# NN22_RPi_DetAdapter03_s00.net
KiCad netlist of a schematic drawn in EAGLE
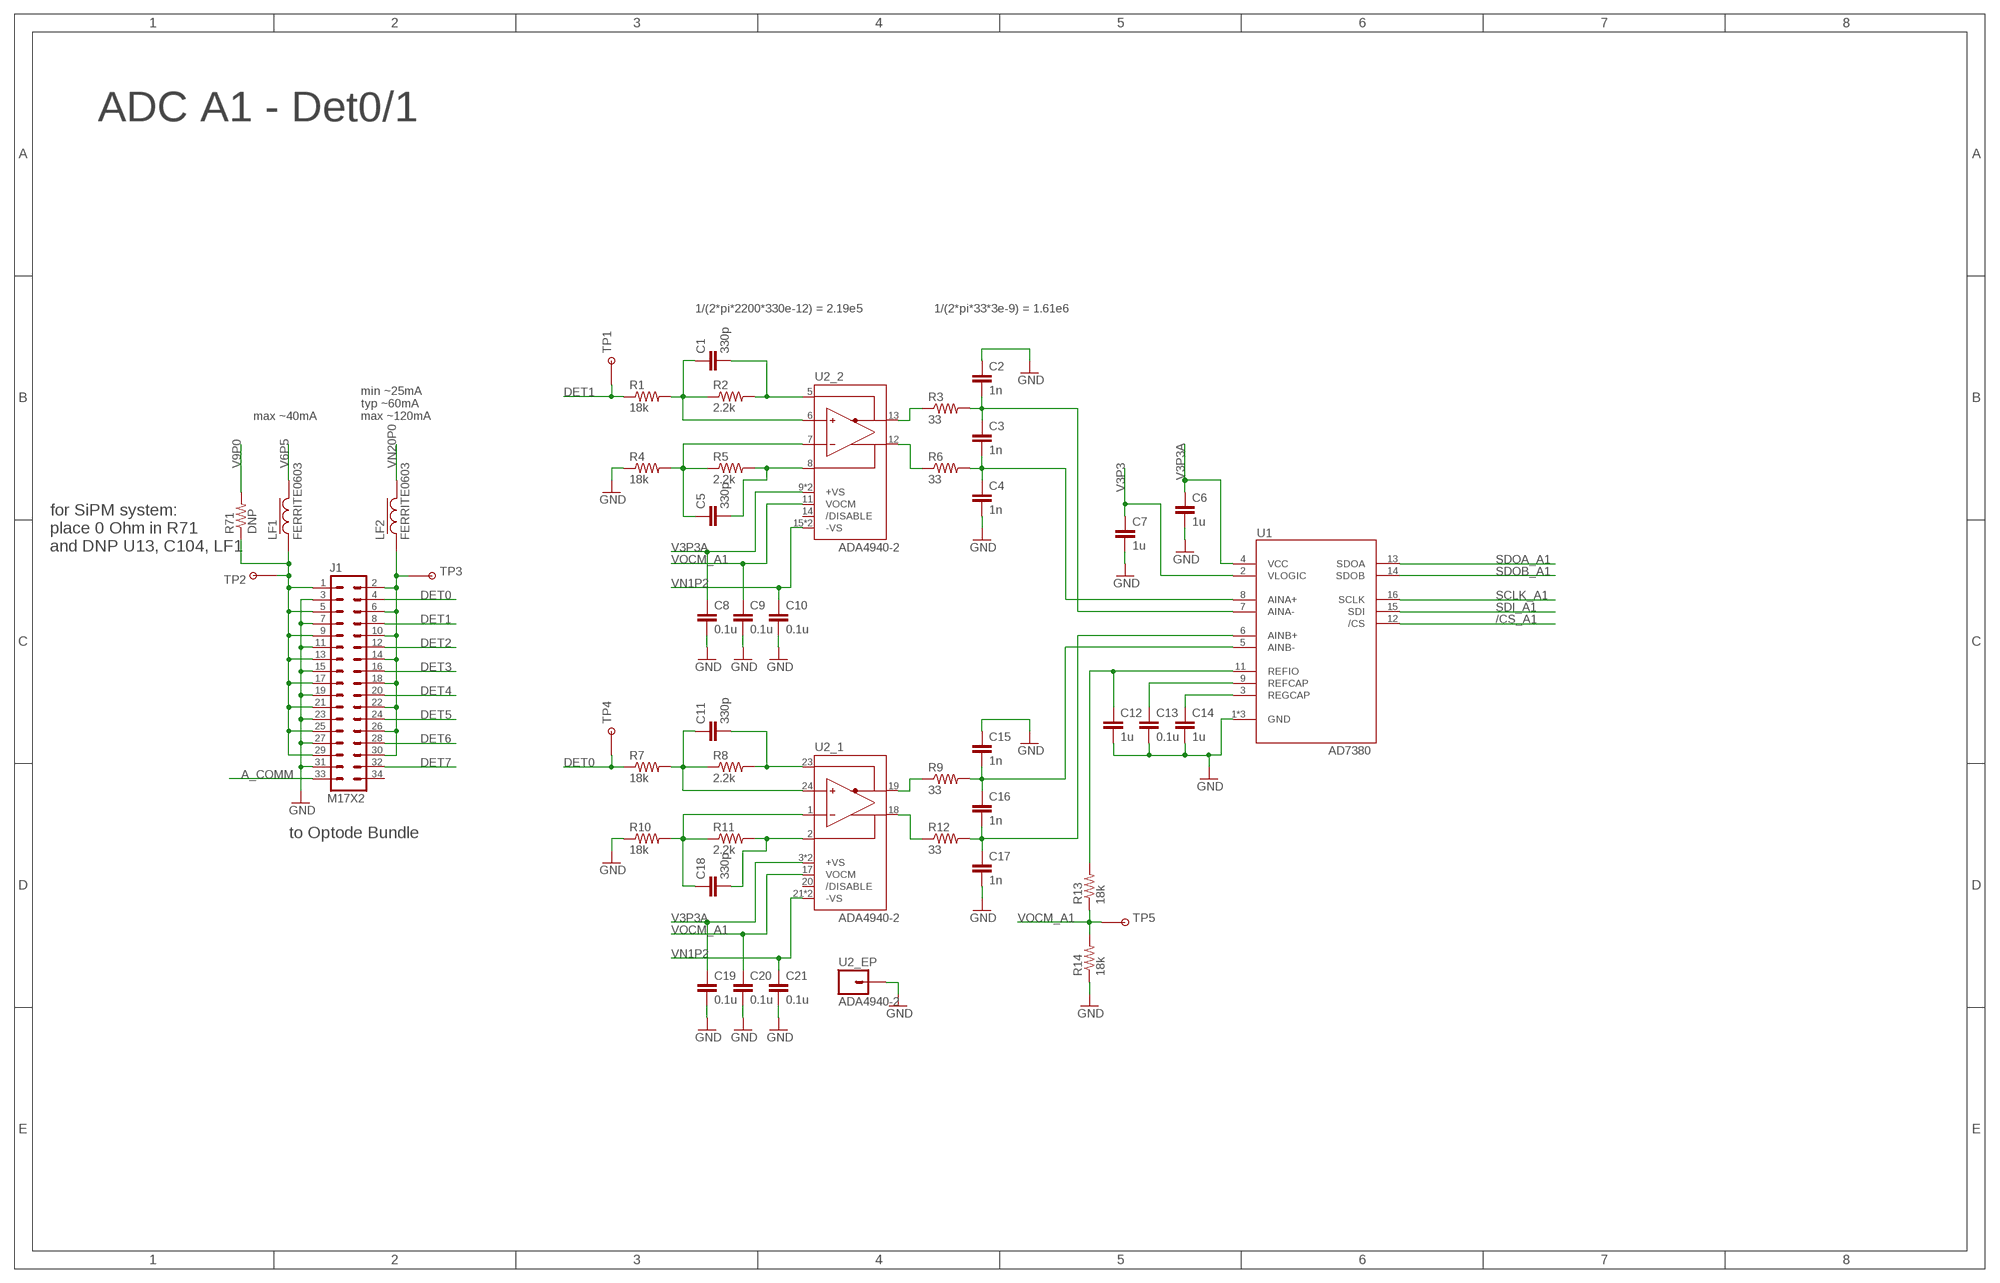
[diagram p0: schematic, sheet 1]
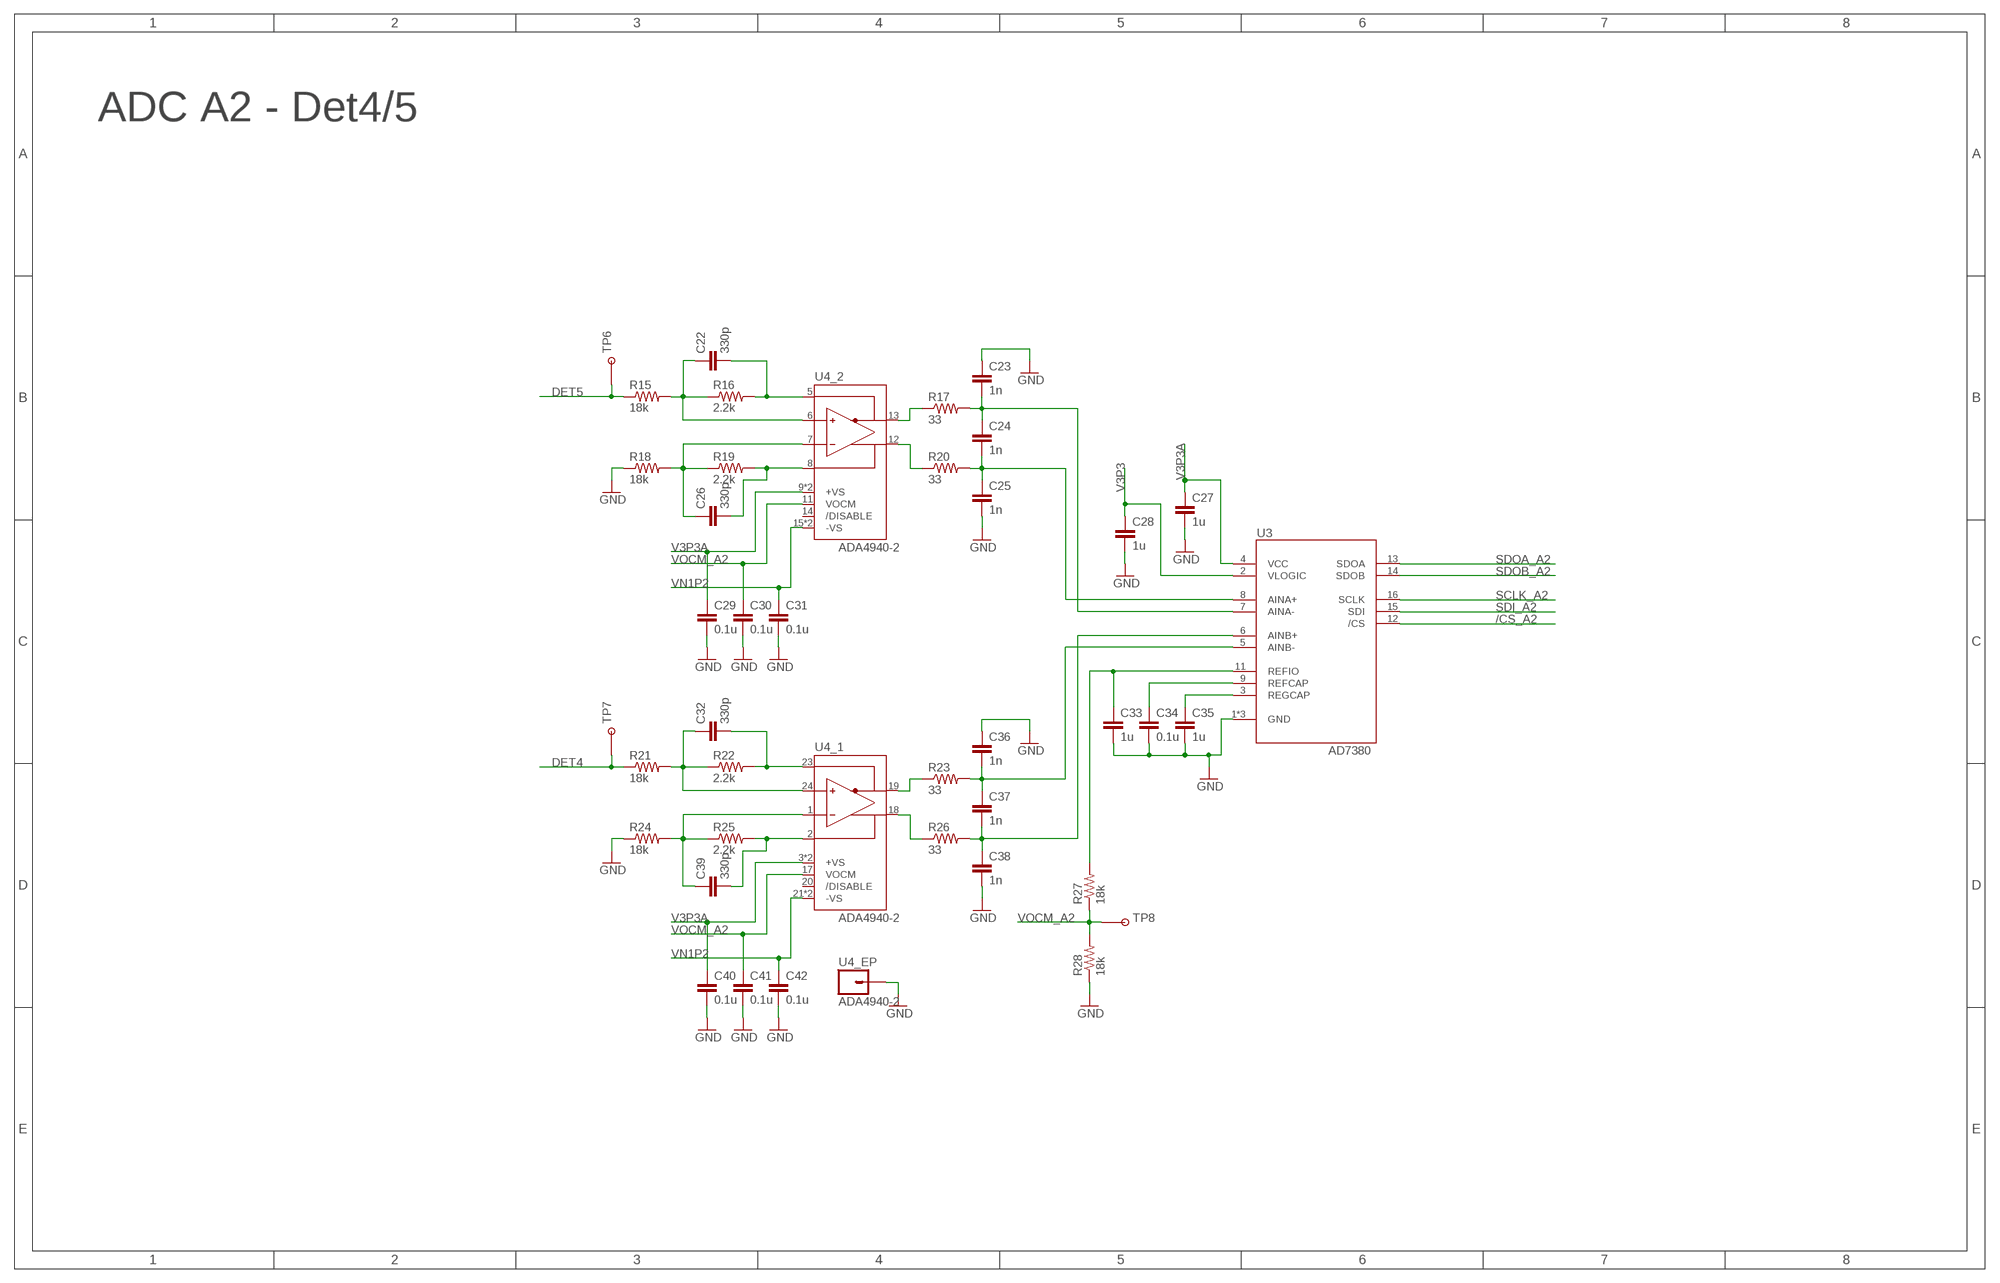
[diagram p1: schematic, sheet 2]
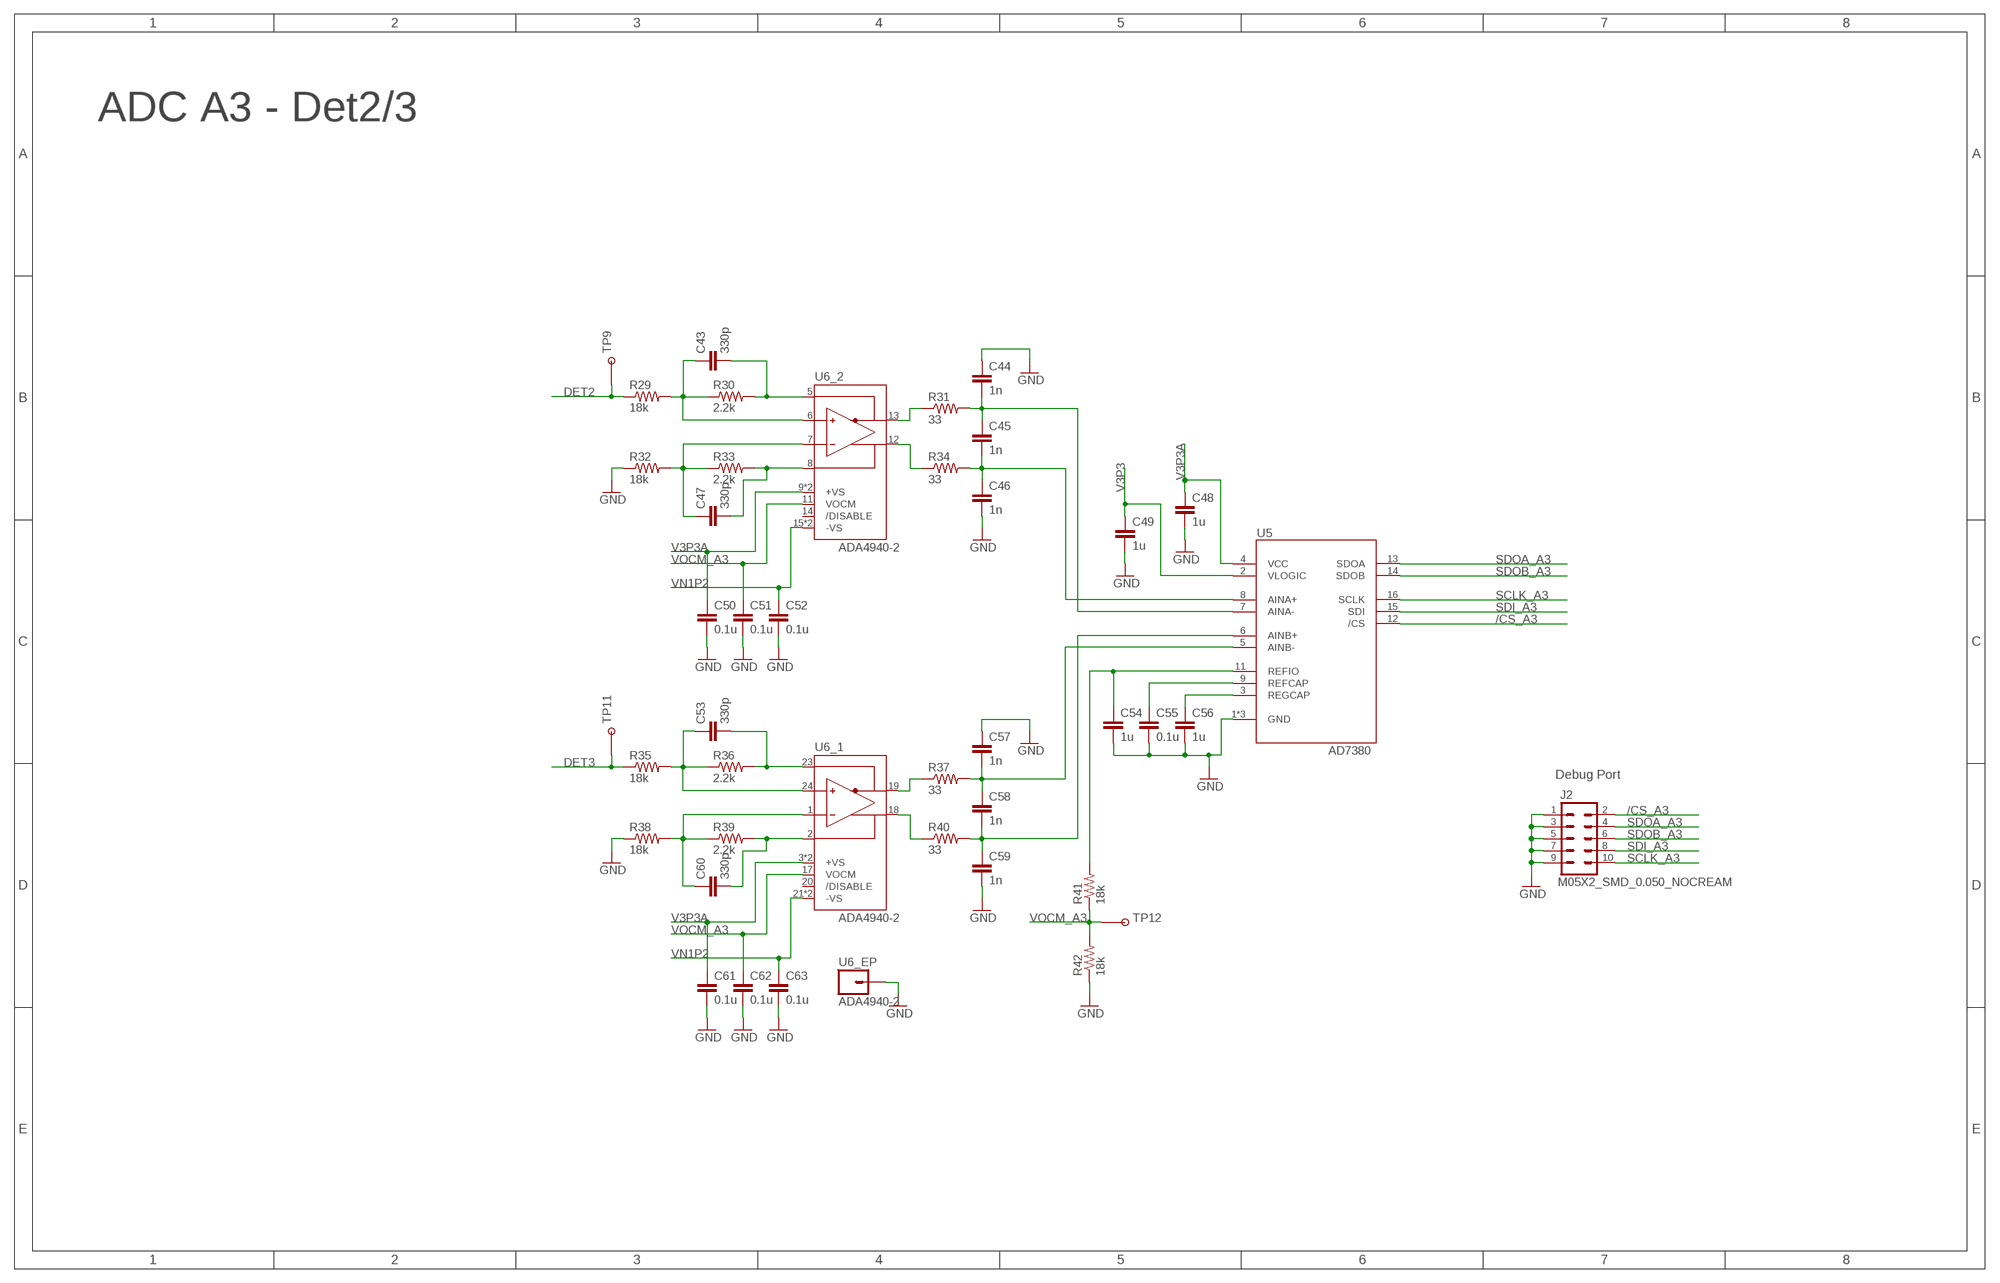
[diagram p2: schematic, sheet 3]
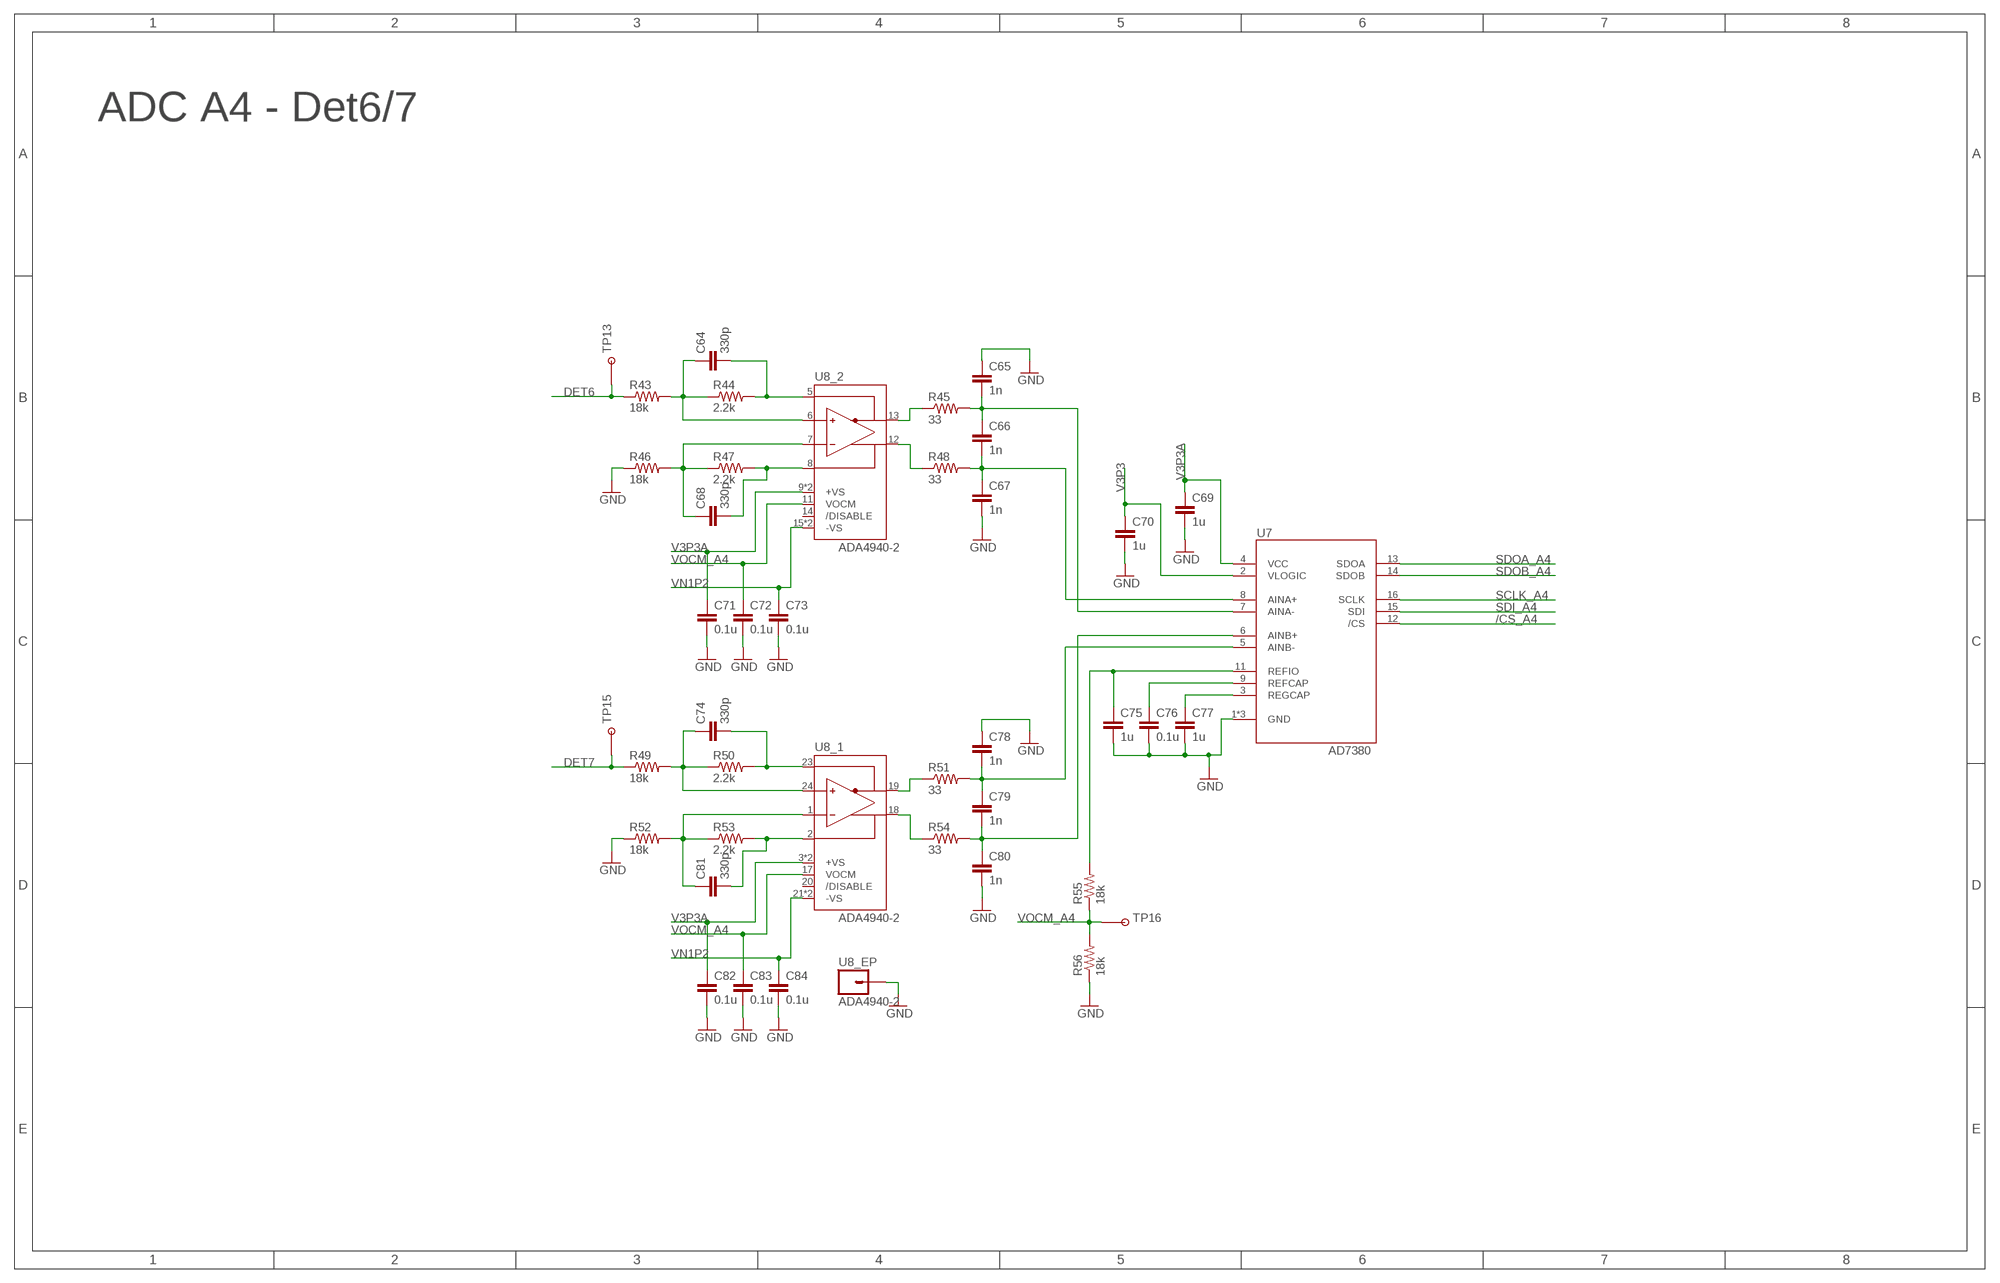
[diagram p3: schematic, sheet 4]
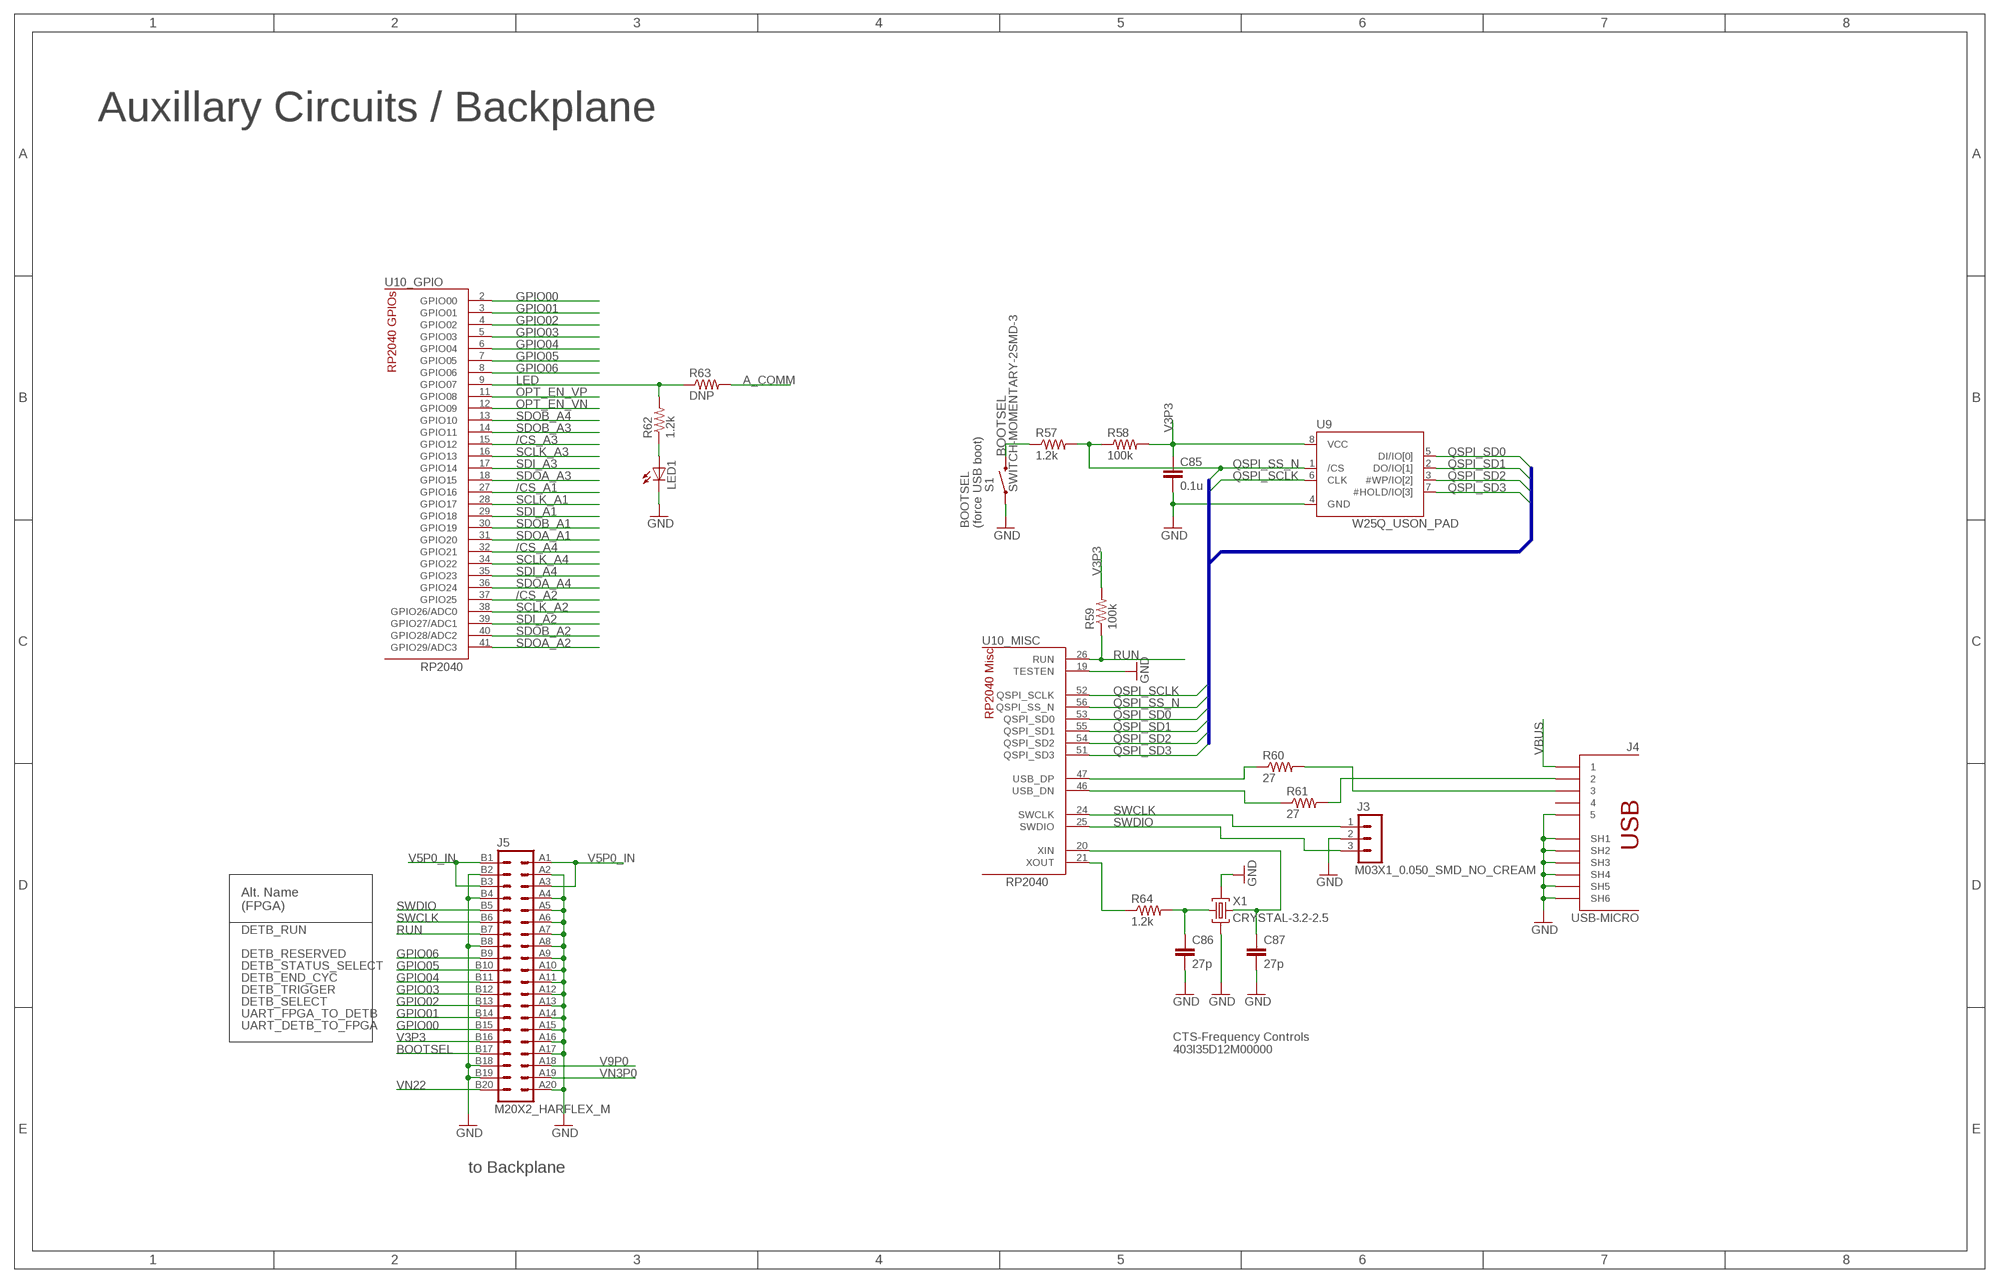
[diagram p4: schematic, sheet 5]
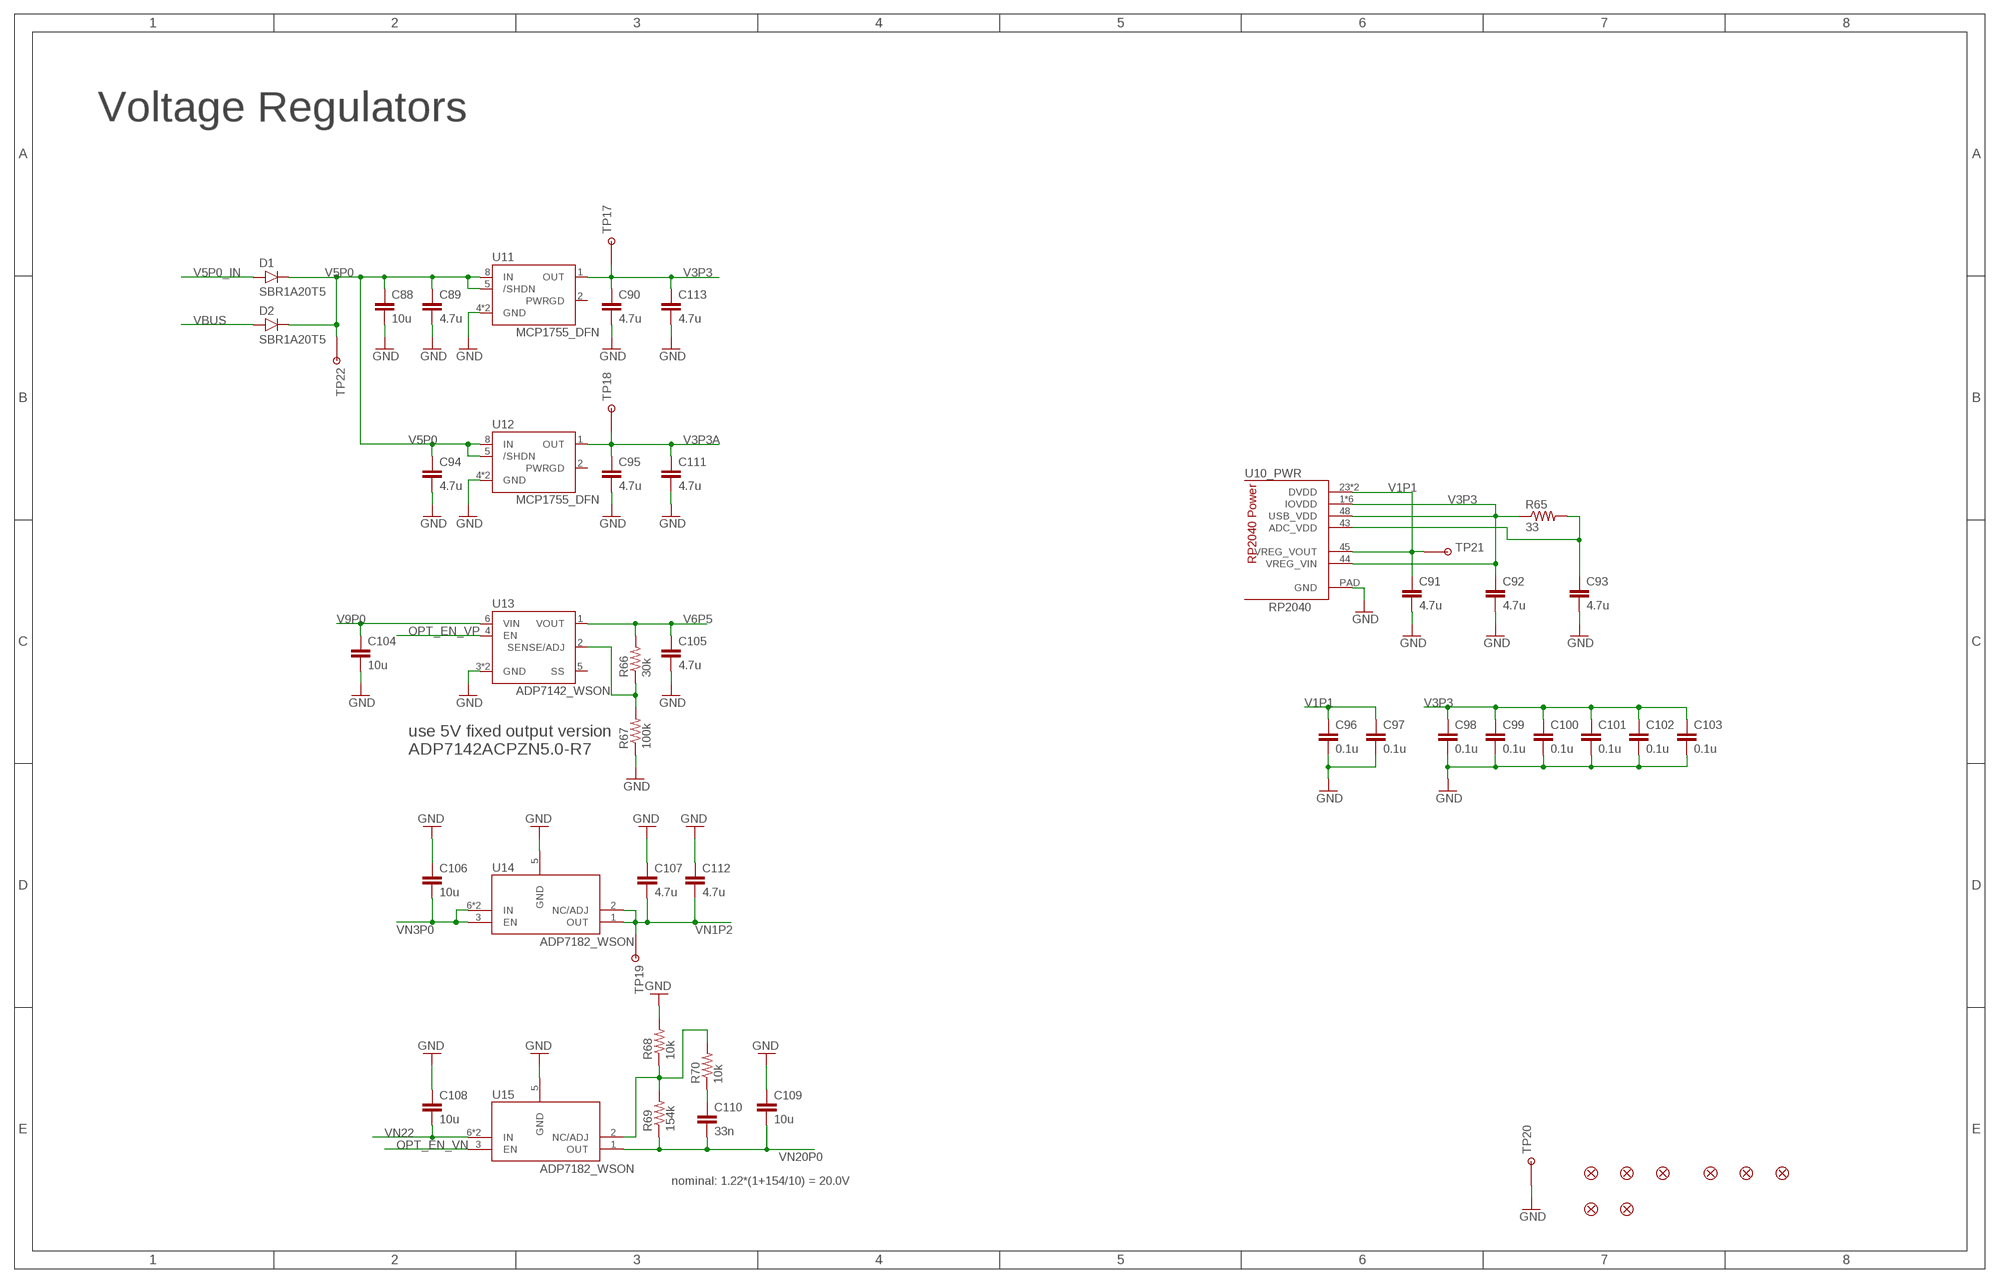
[diagram p5: schematic, sheet 6]

(export (version "E")
  (design (tool "Eeschema 10.0.6"))
  (components
    (comp (ref "C88")
      (value "10u")
      (footprint "eagle-import:0603-CAP")
      (libsource (lib "eagle-import") (part "CAP0603-CAP"))
    )
    (comp (ref "C89")
      (value "4.7u")
      (footprint "eagle-import:0402-CAP")
      (libsource (lib "eagle-import") (part "CAP0402-CAP"))
    )
    (comp (ref "C90")
      (value "4.7u")
      (footprint "eagle-import:0402-CAP")
      (libsource (lib "eagle-import") (part "CAP0402-CAP"))
    )
    (comp (ref "C91")
      (value "4.7u")
      (footprint "eagle-import:0402-CAP")
      (libsource (lib "eagle-import") (part "CAP0402-CAP"))
    )
    (comp (ref "C92")
      (value "4.7u")
      (footprint "eagle-import:0402-CAP")
      (libsource (lib "eagle-import") (part "CAP0402-CAP"))
    )
    (comp (ref "C93")
      (value "4.7u")
      (footprint "eagle-import:0402-CAP")
      (libsource (lib "eagle-import") (part "CAP0402-CAP"))
    )
    (comp (ref "C94")
      (value "4.7u")
      (footprint "eagle-import:0402-CAP")
      (libsource (lib "eagle-import") (part "CAP0402-CAP"))
    )
    (comp (ref "C95")
      (value "4.7u")
      (footprint "eagle-import:0402-CAP")
      (libsource (lib "eagle-import") (part "CAP0402-CAP"))
    )
    (comp (ref "C96")
      (value "0.1u")
      (footprint "eagle-import:0402-CAP")
      (libsource (lib "eagle-import") (part "CAP0402-CAP"))
    )
    (comp (ref "C97")
      (value "0.1u")
      (footprint "eagle-import:0402-CAP")
      (libsource (lib "eagle-import") (part "CAP0402-CAP"))
    )
    (comp (ref "C98")
      (value "0.1u")
      (footprint "eagle-import:0402-CAP")
      (libsource (lib "eagle-import") (part "CAP0402-CAP"))
    )
    (comp (ref "C99")
      (value "0.1u")
      (footprint "eagle-import:0402-CAP")
      (libsource (lib "eagle-import") (part "CAP0402-CAP"))
    )
    (comp (ref "C100")
      (value "0.1u")
      (footprint "eagle-import:0402-CAP")
      (libsource (lib "eagle-import") (part "CAP0402-CAP"))
    )
    (comp (ref "C101")
      (value "0.1u")
      (footprint "eagle-import:0402-CAP")
      (libsource (lib "eagle-import") (part "CAP0402-CAP"))
    )
    (comp (ref "C102")
      (value "0.1u")
      (footprint "eagle-import:0402-CAP")
      (libsource (lib "eagle-import") (part "CAP0402-CAP"))
    )
    (comp (ref "C103")
      (value "0.1u")
      (footprint "eagle-import:0402-CAP")
      (libsource (lib "eagle-import") (part "CAP0402-CAP"))
    )
    (comp (ref "C104")
      (value "10u")
      (footprint "eagle-import:0603-CAP")
      (libsource (lib "eagle-import") (part "CAP0603-CAP"))
    )
    (comp (ref "C105")
      (value "4.7u")
      (footprint "eagle-import:0402-CAP")
      (libsource (lib "eagle-import") (part "CAP0402-CAP"))
    )
    (comp (ref "C106")
      (value "10u")
      (footprint "eagle-import:0603-CAP")
      (libsource (lib "eagle-import") (part "CAP0603-CAP"))
    )
    (comp (ref "C107")
      (value "4.7u")
      (footprint "eagle-import:0402-CAP")
      (libsource (lib "eagle-import") (part "CAP0402-CAP"))
    )
    (comp (ref "C108")
      (value "10u")
      (footprint "eagle-import:0603-CAP")
      (libsource (lib "eagle-import") (part "CAP0603-CAP"))
    )
    (comp (ref "C109")
      (value "10u")
      (footprint "eagle-import:0603-CAP")
      (libsource (lib "eagle-import") (part "CAP0603-CAP"))
    )
    (comp (ref "C110")
      (value "33n")
      (footprint "eagle-import:0402-CAP")
      (libsource (lib "eagle-import") (part "CAP0402-CAP"))
    )
    (comp (ref "C111")
      (value "4.7u")
      (footprint "eagle-import:0402-CAP")
      (libsource (lib "eagle-import") (part "CAP0402-CAP"))
    )
    (comp (ref "C112")
      (value "4.7u")
      (footprint "eagle-import:0402-CAP")
      (libsource (lib "eagle-import") (part "CAP0402-CAP"))
    )
    (comp (ref "C113")
      (value "4.7u")
      (footprint "eagle-import:0402-CAP")
      (libsource (lib "eagle-import") (part "CAP0402-CAP"))
    )
    (comp (ref "D1")
      (value "SBR1A20T5")
      (footprint "eagle-import:SOD523")
      (libsource (lib "eagle-import") (part "DIODE_SOD523"))
    )
    (comp (ref "D2")
      (value "SBR1A20T5")
      (footprint "eagle-import:SOD523")
      (libsource (lib "eagle-import") (part "DIODE_SOD523"))
    )
    (comp (ref "FID1")
      (value "FIDUCIALUFIDUCIAL")
      (footprint "eagle-import:MICRO-FIDUCIAL")
      (libsource (lib "eagle-import") (part "FIDUCIALUFIDUCIAL"))
    )
    (comp (ref "FID2")
      (value "FIDUCIALUFIDUCIAL")
      (footprint "eagle-import:MICRO-FIDUCIAL")
      (libsource (lib "eagle-import") (part "FIDUCIALUFIDUCIAL"))
    )
    (comp (ref "FID3")
      (value "FIDUCIALUFIDUCIAL")
      (footprint "eagle-import:MICRO-FIDUCIAL")
      (libsource (lib "eagle-import") (part "FIDUCIALUFIDUCIAL"))
    )
    (comp (ref "FID4")
      (value "FIDUCIALUFIDUCIAL")
      (footprint "eagle-import:MICRO-FIDUCIAL")
      (libsource (lib "eagle-import") (part "FIDUCIALUFIDUCIAL"))
    )
    (comp (ref "FID5")
      (value "FIDUCIALUFIDUCIAL")
      (footprint "eagle-import:MICRO-FIDUCIAL")
      (libsource (lib "eagle-import") (part "FIDUCIALUFIDUCIAL"))
    )
    (comp (ref "FID6")
      (value "FIDUCIALUFIDUCIAL")
      (footprint "eagle-import:MICRO-FIDUCIAL")
      (libsource (lib "eagle-import") (part "FIDUCIALUFIDUCIAL"))
    )
    (comp (ref "FID7")
      (value "FIDUCIALUFIDUCIAL")
      (footprint "eagle-import:MICRO-FIDUCIAL")
      (libsource (lib "eagle-import") (part "FIDUCIALUFIDUCIAL"))
    )
    (comp (ref "FID8")
      (value "FIDUCIALUFIDUCIAL")
      (footprint "eagle-import:MICRO-FIDUCIAL")
      (libsource (lib "eagle-import") (part "FIDUCIALUFIDUCIAL"))
    )
    (comp (ref "R65")
      (value "33")
      (footprint "eagle-import:0402-RES")
      (libsource (lib "eagle-import") (part "RESISTOR0402-RES"))
    )
    (comp (ref "R66")
      (value "30k")
      (footprint "eagle-import:0402-RES")
      (libsource (lib "eagle-import") (part "RESISTOR0402-RES"))
    )
    (comp (ref "R67")
      (value "100k")
      (footprint "eagle-import:0402-RES")
      (libsource (lib "eagle-import") (part "RESISTOR0402-RES"))
    )
    (comp (ref "R68")
      (value "10k")
      (footprint "eagle-import:0402-RES")
      (libsource (lib "eagle-import") (part "RESISTOR0402-RES"))
    )
    (comp (ref "R69")
      (value "154k")
      (footprint "eagle-import:0402-RES")
      (libsource (lib "eagle-import") (part "RESISTOR0402-RES"))
    )
    (comp (ref "R70")
      (value "10k")
      (footprint "eagle-import:0402-RES")
      (libsource (lib "eagle-import") (part "RESISTOR0402-RES"))
    )
    (comp (ref "TP17")
      (value "TESTPOINT_ROUND")
      (footprint "eagle-import:TESTPAD_ROUND")
      (libsource (lib "eagle-import") (part "TESTPOINT_ROUND"))
    )
    (comp (ref "TP18")
      (value "TESTPOINT_ROUND")
      (footprint "eagle-import:TESTPAD_ROUND")
      (libsource (lib "eagle-import") (part "TESTPOINT_ROUND"))
    )
    (comp (ref "TP19")
      (value "TESTPOINT_ROUND")
      (footprint "eagle-import:TESTPAD_ROUND")
      (libsource (lib "eagle-import") (part "TESTPOINT_ROUND"))
    )
    (comp (ref "TP20")
      (value "TESTPOINT1X01")
      (footprint "eagle-import:1X01")
      (libsource (lib "eagle-import") (part "TESTPOINT1X01"))
    )
    (comp (ref "TP21")
      (value "TESTPOINTPADSMALL")
      (footprint "eagle-import:TESTPAD_SMALL")
      (libsource (lib "eagle-import") (part "TESTPOINTPADSMALL"))
    )
    (comp (ref "TP22")
      (value "TESTPOINT_ROUND")
      (footprint "eagle-import:TESTPAD_ROUND")
      (libsource (lib "eagle-import") (part "TESTPOINT_ROUND"))
    )
    (comp (ref "U10")
      (value "RP2040")
      (footprint "eagle-import:QFN-56_EP")
      (libsource (lib "eagle-import") (part "RP2040"))
    )
    (comp (ref "U11")
      (value "MCP1755_DFN")
      (footprint "eagle-import:DFN8_2X3MM")
      (libsource (lib "eagle-import") (part "MCP1755_DFN"))
    )
    (comp (ref "U12")
      (value "MCP1755_DFN")
      (footprint "eagle-import:DFN8_2X3MM")
      (libsource (lib "eagle-import") (part "MCP1755_DFN"))
    )
    (comp (ref "U13")
      (value "ADP7142_WSON")
      (footprint "eagle-import:WSON6")
      (libsource (lib "eagle-import") (part "ADP7142_WSON"))
    )
    (comp (ref "U14")
      (value "ADP7182_WSON")
      (footprint "eagle-import:WSON6")
      (libsource (lib "eagle-import") (part "ADP7182_WSON"))
    )
    (comp (ref "U15")
      (value "ADP7182_WSON")
      (footprint "eagle-import:WSON6")
      (libsource (lib "eagle-import") (part "ADP7182_WSON"))
    )
    (comp (ref "C1")
      (value "330p")
      (footprint "eagle-import:0402-CAP")
      (libsource (lib "eagle-import") (part "CAP0402-CAP"))
    )
    (comp (ref "C2")
      (value "1n")
      (footprint "eagle-import:0402-CAP")
      (libsource (lib "eagle-import") (part "CAP0402-CAP"))
    )
    (comp (ref "C3")
      (value "1n")
      (footprint "eagle-import:0402-CAP")
      (libsource (lib "eagle-import") (part "CAP0402-CAP"))
    )
    (comp (ref "C4")
      (value "1n")
      (footprint "eagle-import:0402-CAP")
      (libsource (lib "eagle-import") (part "CAP0402-CAP"))
    )
    (comp (ref "C5")
      (value "330p")
      (footprint "eagle-import:0402-CAP")
      (libsource (lib "eagle-import") (part "CAP0402-CAP"))
    )
    (comp (ref "C6")
      (value "1u")
      (footprint "eagle-import:0402-CAP")
      (libsource (lib "eagle-import") (part "CAP0402-CAP"))
    )
    (comp (ref "C7")
      (value "1u")
      (footprint "eagle-import:0402-CAP")
      (libsource (lib "eagle-import") (part "CAP0402-CAP"))
    )
    (comp (ref "C8")
      (value "0.1u")
      (footprint "eagle-import:0402-CAP")
      (libsource (lib "eagle-import") (part "CAP0402-CAP"))
    )
    (comp (ref "C9")
      (value "0.1u")
      (footprint "eagle-import:0402-CAP")
      (libsource (lib "eagle-import") (part "CAP0402-CAP"))
    )
    (comp (ref "C10")
      (value "0.1u")
      (footprint "eagle-import:0402-CAP")
      (libsource (lib "eagle-import") (part "CAP0402-CAP"))
    )
    (comp (ref "C11")
      (value "330p")
      (footprint "eagle-import:0402-CAP")
      (libsource (lib "eagle-import") (part "CAP0402-CAP"))
    )
    (comp (ref "C12")
      (value "1u")
      (footprint "eagle-import:0402-CAP")
      (libsource (lib "eagle-import") (part "CAP0402-CAP"))
    )
    (comp (ref "C13")
      (value "0.1u")
      (footprint "eagle-import:0402-CAP")
      (libsource (lib "eagle-import") (part "CAP0402-CAP"))
    )
    (comp (ref "C14")
      (value "1u")
      (footprint "eagle-import:0402-CAP")
      (libsource (lib "eagle-import") (part "CAP0402-CAP"))
    )
    (comp (ref "C15")
      (value "1n")
      (footprint "eagle-import:0402-CAP")
      (libsource (lib "eagle-import") (part "CAP0402-CAP"))
    )
    (comp (ref "C16")
      (value "1n")
      (footprint "eagle-import:0402-CAP")
      (libsource (lib "eagle-import") (part "CAP0402-CAP"))
    )
    (comp (ref "C17")
      (value "1n")
      (footprint "eagle-import:0402-CAP")
      (libsource (lib "eagle-import") (part "CAP0402-CAP"))
    )
    (comp (ref "C18")
      (value "330p")
      (footprint "eagle-import:0402-CAP")
      (libsource (lib "eagle-import") (part "CAP0402-CAP"))
    )
    (comp (ref "C19")
      (value "0.1u")
      (footprint "eagle-import:0402-CAP")
      (libsource (lib "eagle-import") (part "CAP0402-CAP"))
    )
    (comp (ref "C20")
      (value "0.1u")
      (footprint "eagle-import:0402-CAP")
      (libsource (lib "eagle-import") (part "CAP0402-CAP"))
    )
    (comp (ref "C21")
      (value "0.1u")
      (footprint "eagle-import:0402-CAP")
      (libsource (lib "eagle-import") (part "CAP0402-CAP"))
    )
    (comp (ref "J1")
      (value "M17X2")
      (footprint "eagle-import:M17X2_0.050_SHF")
      (libsource (lib "eagle-import") (part "M17X2"))
    )
    (comp (ref "LF1")
      (value "FERRITE0603")
      (footprint "eagle-import:0603-FER")
      (libsource (lib "eagle-import") (part "FERRITE0603"))
    )
    (comp (ref "LF2")
      (value "FERRITE0603")
      (footprint "eagle-import:0603-FER")
      (libsource (lib "eagle-import") (part "FERRITE0603"))
    )
    (comp (ref "R1")
      (value "18k")
      (footprint "eagle-import:0402-RES")
      (libsource (lib "eagle-import") (part "RESISTOR0402-RES"))
    )
    (comp (ref "R2")
      (value "2.2k")
      (footprint "eagle-import:0402-RES")
      (libsource (lib "eagle-import") (part "RESISTOR0402-RES"))
    )
    (comp (ref "R3")
      (value "33")
      (footprint "eagle-import:0402-RES")
      (libsource (lib "eagle-import") (part "RESISTOR0402-RES"))
    )
    (comp (ref "R4")
      (value "18k")
      (footprint "eagle-import:0402-RES")
      (libsource (lib "eagle-import") (part "RESISTOR0402-RES"))
    )
    (comp (ref "R5")
      (value "2.2k")
      (footprint "eagle-import:0402-RES")
      (libsource (lib "eagle-import") (part "RESISTOR0402-RES"))
    )
    (comp (ref "R6")
      (value "33")
      (footprint "eagle-import:0402-RES")
      (libsource (lib "eagle-import") (part "RESISTOR0402-RES"))
    )
    (comp (ref "R7")
      (value "18k")
      (footprint "eagle-import:0402-RES")
      (libsource (lib "eagle-import") (part "RESISTOR0402-RES"))
    )
    (comp (ref "R8")
      (value "2.2k")
      (footprint "eagle-import:0402-RES")
      (libsource (lib "eagle-import") (part "RESISTOR0402-RES"))
    )
    (comp (ref "R9")
      (value "33")
      (footprint "eagle-import:0402-RES")
      (libsource (lib "eagle-import") (part "RESISTOR0402-RES"))
    )
    (comp (ref "R10")
      (value "18k")
      (footprint "eagle-import:0402-RES")
      (libsource (lib "eagle-import") (part "RESISTOR0402-RES"))
    )
    (comp (ref "R11")
      (value "2.2k")
      (footprint "eagle-import:0402-RES")
      (libsource (lib "eagle-import") (part "RESISTOR0402-RES"))
    )
    (comp (ref "R12")
      (value "33")
      (footprint "eagle-import:0402-RES")
      (libsource (lib "eagle-import") (part "RESISTOR0402-RES"))
    )
    (comp (ref "R13")
      (value "18k")
      (footprint "eagle-import:0402-RES")
      (libsource (lib "eagle-import") (part "RESISTOR0402-RES"))
    )
    (comp (ref "R14")
      (value "18k")
      (footprint "eagle-import:0402-RES")
      (libsource (lib "eagle-import") (part "RESISTOR0402-RES"))
    )
    (comp (ref "R71")
      (value "DNP")
      (footprint "eagle-import:0402-RES")
      (libsource (lib "eagle-import") (part "RESISTOR0402-RES"))
    )
    (comp (ref "TP1")
      (value "TESTPOINT_ROUND")
      (footprint "eagle-import:TESTPAD_ROUND")
      (libsource (lib "eagle-import") (part "TESTPOINT_ROUND"))
    )
    (comp (ref "TP2")
      (value "TESTPOINT_ROUND")
      (footprint "eagle-import:TESTPAD_ROUND")
      (libsource (lib "eagle-import") (part "TESTPOINT_ROUND"))
    )
    (comp (ref "TP3")
      (value "TESTPOINT_ROUND")
      (footprint "eagle-import:TESTPAD_ROUND")
      (libsource (lib "eagle-import") (part "TESTPOINT_ROUND"))
    )
    (comp (ref "TP4")
      (value "TESTPOINT_ROUND")
      (footprint "eagle-import:TESTPAD_ROUND")
      (libsource (lib "eagle-import") (part "TESTPOINT_ROUND"))
    )
    (comp (ref "TP5")
      (value "TESTPOINT_ROUND")
      (footprint "eagle-import:TESTPAD_ROUND")
      (libsource (lib "eagle-import") (part "TESTPOINT_ROUND"))
    )
    (comp (ref "U1")
      (value "AD7380")
      (footprint "eagle-import:LFCSP16")
      (libsource (lib "eagle-import") (part "AD7380"))
    )
    (comp (ref "U2")
      (value "ADA4940-2")
      (footprint "eagle-import:LFCSP24")
      (libsource (lib "eagle-import") (part "ADA4940-2"))
    )
    (comp (ref "C64")
      (value "330p")
      (footprint "eagle-import:0402-CAP")
      (libsource (lib "eagle-import") (part "CAP0402-CAP"))
    )
    (comp (ref "C65")
      (value "1n")
      (footprint "eagle-import:0402-CAP")
      (libsource (lib "eagle-import") (part "CAP0402-CAP"))
    )
    (comp (ref "C66")
      (value "1n")
      (footprint "eagle-import:0402-CAP")
      (libsource (lib "eagle-import") (part "CAP0402-CAP"))
    )
    (comp (ref "C67")
      (value "1n")
      (footprint "eagle-import:0402-CAP")
      (libsource (lib "eagle-import") (part "CAP0402-CAP"))
    )
    (comp (ref "C68")
      (value "330p")
      (footprint "eagle-import:0402-CAP")
      (libsource (lib "eagle-import") (part "CAP0402-CAP"))
    )
    (comp (ref "C69")
      (value "1u")
      (footprint "eagle-import:0402-CAP")
      (libsource (lib "eagle-import") (part "CAP0402-CAP"))
    )
    (comp (ref "C70")
      (value "1u")
      (footprint "eagle-import:0402-CAP")
      (libsource (lib "eagle-import") (part "CAP0402-CAP"))
    )
    (comp (ref "C71")
      (value "0.1u")
      (footprint "eagle-import:0402-CAP")
      (libsource (lib "eagle-import") (part "CAP0402-CAP"))
    )
    (comp (ref "C72")
      (value "0.1u")
      (footprint "eagle-import:0402-CAP")
      (libsource (lib "eagle-import") (part "CAP0402-CAP"))
    )
    (comp (ref "C73")
      (value "0.1u")
      (footprint "eagle-import:0402-CAP")
      (libsource (lib "eagle-import") (part "CAP0402-CAP"))
    )
    (comp (ref "C74")
      (value "330p")
      (footprint "eagle-import:0402-CAP")
      (libsource (lib "eagle-import") (part "CAP0402-CAP"))
    )
    (comp (ref "C75")
      (value "1u")
      (footprint "eagle-import:0402-CAP")
      (libsource (lib "eagle-import") (part "CAP0402-CAP"))
    )
    (comp (ref "C76")
      (value "0.1u")
      (footprint "eagle-import:0402-CAP")
      (libsource (lib "eagle-import") (part "CAP0402-CAP"))
    )
    (comp (ref "C77")
      (value "1u")
      (footprint "eagle-import:0402-CAP")
      (libsource (lib "eagle-import") (part "CAP0402-CAP"))
    )
    (comp (ref "C78")
      (value "1n")
      (footprint "eagle-import:0402-CAP")
      (libsource (lib "eagle-import") (part "CAP0402-CAP"))
    )
    (comp (ref "C79")
      (value "1n")
      (footprint "eagle-import:0402-CAP")
      (libsource (lib "eagle-import") (part "CAP0402-CAP"))
    )
    (comp (ref "C80")
      (value "1n")
      (footprint "eagle-import:0402-CAP")
      (libsource (lib "eagle-import") (part "CAP0402-CAP"))
    )
    (comp (ref "C81")
      (value "330p")
      (footprint "eagle-import:0402-CAP")
      (libsource (lib "eagle-import") (part "CAP0402-CAP"))
    )
    (comp (ref "C82")
      (value "0.1u")
      (footprint "eagle-import:0402-CAP")
      (libsource (lib "eagle-import") (part "CAP0402-CAP"))
    )
    (comp (ref "C83")
      (value "0.1u")
      (footprint "eagle-import:0402-CAP")
      (libsource (lib "eagle-import") (part "CAP0402-CAP"))
    )
    (comp (ref "C84")
      (value "0.1u")
      (footprint "eagle-import:0402-CAP")
      (libsource (lib "eagle-import") (part "CAP0402-CAP"))
    )
    (comp (ref "R43")
      (value "18k")
      (footprint "eagle-import:0402-RES")
      (libsource (lib "eagle-import") (part "RESISTOR0402-RES"))
    )
    (comp (ref "R44")
      (value "2.2k")
      (footprint "eagle-import:0402-RES")
      (libsource (lib "eagle-import") (part "RESISTOR0402-RES"))
    )
    (comp (ref "R45")
      (value "33")
      (footprint "eagle-import:0402-RES")
      (libsource (lib "eagle-import") (part "RESISTOR0402-RES"))
    )
    (comp (ref "R46")
      (value "18k")
      (footprint "eagle-import:0402-RES")
      (libsource (lib "eagle-import") (part "RESISTOR0402-RES"))
    )
    (comp (ref "R47")
      (value "2.2k")
      (footprint "eagle-import:0402-RES")
      (libsource (lib "eagle-import") (part "RESISTOR0402-RES"))
    )
    (comp (ref "R48")
      (value "33")
      (footprint "eagle-import:0402-RES")
      (libsource (lib "eagle-import") (part "RESISTOR0402-RES"))
    )
    (comp (ref "R49")
      (value "18k")
      (footprint "eagle-import:0402-RES")
      (libsource (lib "eagle-import") (part "RESISTOR0402-RES"))
    )
    (comp (ref "R50")
      (value "2.2k")
      (footprint "eagle-import:0402-RES")
      (libsource (lib "eagle-import") (part "RESISTOR0402-RES"))
    )
    (comp (ref "R51")
      (value "33")
      (footprint "eagle-import:0402-RES")
      (libsource (lib "eagle-import") (part "RESISTOR0402-RES"))
    )
    (comp (ref "R52")
      (value "18k")
      (footprint "eagle-import:0402-RES")
      (libsource (lib "eagle-import") (part "RESISTOR0402-RES"))
    )
    (comp (ref "R53")
      (value "2.2k")
      (footprint "eagle-import:0402-RES")
      (libsource (lib "eagle-import") (part "RESISTOR0402-RES"))
    )
    (comp (ref "R54")
      (value "33")
      (footprint "eagle-import:0402-RES")
      (libsource (lib "eagle-import") (part "RESISTOR0402-RES"))
    )
    (comp (ref "R55")
      (value "18k")
      (footprint "eagle-import:0402-RES")
      (libsource (lib "eagle-import") (part "RESISTOR0402-RES"))
    )
    (comp (ref "R56")
      (value "18k")
      (footprint "eagle-import:0402-RES")
      (libsource (lib "eagle-import") (part "RESISTOR0402-RES"))
    )
    (comp (ref "TP13")
      (value "TESTPOINT_ROUND")
      (footprint "eagle-import:TESTPAD_ROUND")
      (libsource (lib "eagle-import") (part "TESTPOINT_ROUND"))
    )
    (comp (ref "TP15")
      (value "TESTPOINT_ROUND")
      (footprint "eagle-import:TESTPAD_ROUND")
      (libsource (lib "eagle-import") (part "TESTPOINT_ROUND"))
    )
    (comp (ref "TP16")
      (value "TESTPOINT_ROUND")
      (footprint "eagle-import:TESTPAD_ROUND")
      (libsource (lib "eagle-import") (part "TESTPOINT_ROUND"))
    )
    (comp (ref "U7")
      (value "AD7380")
      (footprint "eagle-import:LFCSP16")
      (libsource (lib "eagle-import") (part "AD7380"))
    )
    (comp (ref "U8")
      (value "ADA4940-2")
      (footprint "eagle-import:LFCSP24")
      (libsource (lib "eagle-import") (part "ADA4940-2"))
    )
    (comp (ref "C85")
      (value "0.1u")
      (footprint "eagle-import:0402-CAP")
      (libsource (lib "eagle-import") (part "CAP0402-CAP"))
    )
    (comp (ref "C86")
      (value "27p")
      (footprint "eagle-import:0402-CAP")
      (libsource (lib "eagle-import") (part "CAP0402-CAP"))
    )
    (comp (ref "C87")
      (value "27p")
      (footprint "eagle-import:0402-CAP")
      (libsource (lib "eagle-import") (part "CAP0402-CAP"))
    )
    (comp (ref "J3")
      (value "M03X1_0.050_SMD_NO_CREAM")
      (footprint "eagle-import:M03X1_0.050_SMD_NO_CREAM")
      (libsource (lib "eagle-import") (part "M03X1_0.050_SMD_NO_CREAM"))
    )
    (comp (ref "J4")
      (value "USB-MICRO")
      (footprint "eagle-import:USB-MICRO")
      (libsource (lib "eagle-import") (part "USB-MICRO"))
    )
    (comp (ref "J5")
      (value "M20X2_HARFLEX_M")
      (footprint "eagle-import:M20X2_HARFLEX_M")
      (libsource (lib "eagle-import") (part "M20X2_HARFLEX_M"))
    )
    (comp (ref "LED1")
      (value "LED0603")
      (footprint "eagle-import:LED-0603")
      (libsource (lib "eagle-import") (part "LED0603"))
    )
    (comp (ref "R57")
      (value "1.2k")
      (footprint "eagle-import:0402-RES")
      (libsource (lib "eagle-import") (part "RESISTOR0402-RES"))
    )
    (comp (ref "R58")
      (value "100k")
      (footprint "eagle-import:0402-RES")
      (libsource (lib "eagle-import") (part "RESISTOR0402-RES"))
    )
    (comp (ref "R59")
      (value "100k")
      (footprint "eagle-import:0402-RES")
      (libsource (lib "eagle-import") (part "RESISTOR0402-RES"))
    )
    (comp (ref "R60")
      (value "27")
      (footprint "eagle-import:0402-RES")
      (libsource (lib "eagle-import") (part "RESISTOR0402-RES"))
    )
    (comp (ref "R61")
      (value "27")
      (footprint "eagle-import:0402-RES")
      (libsource (lib "eagle-import") (part "RESISTOR0402-RES"))
    )
    (comp (ref "R62")
      (value "1.2k")
      (footprint "eagle-import:0402-RES")
      (libsource (lib "eagle-import") (part "RESISTOR0402-RES"))
    )
    (comp (ref "R63")
      (value "DNP")
      (footprint "eagle-import:0402-RES")
      (libsource (lib "eagle-import") (part "RESISTOR0402-RES"))
    )
    (comp (ref "R64")
      (value "1.2k")
      (footprint "eagle-import:0402-RES")
      (libsource (lib "eagle-import") (part "RESISTOR0402-RES"))
    )
    (comp (ref "S1")
      (value "SWITCH-MOMENTARY-2SMD-3")
      (footprint "eagle-import:TACTILE_SWITCH_SMD-3")
      (libsource (lib "eagle-import") (part "SWITCH-MOMENTARY-2SMD-3"))
    )
    (comp (ref "U9")
      (value "W25Q_USON_PAD")
      (footprint "eagle-import:USON8L-2X3MM_APM")
      (libsource (lib "eagle-import") (part "W25Q_USON_PAD"))
    )
    (comp (ref "X1")
      (value "CRYSTAL-3.2-2.5")
      (footprint "eagle-import:CRYSTAL-3.2-2.5")
      (libsource (lib "eagle-import") (part "CRYSTAL-3.2-2.5"))
    )
    (comp (ref "C43")
      (value "330p")
      (footprint "eagle-import:0402-CAP")
      (libsource (lib "eagle-import") (part "CAP0402-CAP"))
    )
    (comp (ref "C44")
      (value "1n")
      (footprint "eagle-import:0402-CAP")
      (libsource (lib "eagle-import") (part "CAP0402-CAP"))
    )
    (comp (ref "C45")
      (value "1n")
      (footprint "eagle-import:0402-CAP")
      (libsource (lib "eagle-import") (part "CAP0402-CAP"))
    )
    (comp (ref "C46")
      (value "1n")
      (footprint "eagle-import:0402-CAP")
      (libsource (lib "eagle-import") (part "CAP0402-CAP"))
    )
    (comp (ref "C47")
      (value "330p")
      (footprint "eagle-import:0402-CAP")
      (libsource (lib "eagle-import") (part "CAP0402-CAP"))
    )
    (comp (ref "C48")
      (value "1u")
      (footprint "eagle-import:0402-CAP")
      (libsource (lib "eagle-import") (part "CAP0402-CAP"))
    )
    (comp (ref "C49")
      (value "1u")
      (footprint "eagle-import:0402-CAP")
      (libsource (lib "eagle-import") (part "CAP0402-CAP"))
    )
    (comp (ref "C50")
      (value "0.1u")
      (footprint "eagle-import:0402-CAP")
      (libsource (lib "eagle-import") (part "CAP0402-CAP"))
    )
    (comp (ref "C51")
      (value "0.1u")
      (footprint "eagle-import:0402-CAP")
      (libsource (lib "eagle-import") (part "CAP0402-CAP"))
    )
    (comp (ref "C52")
      (value "0.1u")
      (footprint "eagle-import:0402-CAP")
      (libsource (lib "eagle-import") (part "CAP0402-CAP"))
    )
    (comp (ref "C53")
      (value "330p")
      (footprint "eagle-import:0402-CAP")
      (libsource (lib "eagle-import") (part "CAP0402-CAP"))
    )
    (comp (ref "C54")
      (value "1u")
      (footprint "eagle-import:0402-CAP")
      (libsource (lib "eagle-import") (part "CAP0402-CAP"))
    )
    (comp (ref "C55")
      (value "0.1u")
      (footprint "eagle-import:0402-CAP")
      (libsource (lib "eagle-import") (part "CAP0402-CAP"))
    )
    (comp (ref "C56")
      (value "1u")
      (footprint "eagle-import:0402-CAP")
      (libsource (lib "eagle-import") (part "CAP0402-CAP"))
    )
    (comp (ref "C57")
      (value "1n")
      (footprint "eagle-import:0402-CAP")
      (libsource (lib "eagle-import") (part "CAP0402-CAP"))
    )
    (comp (ref "C58")
      (value "1n")
      (footprint "eagle-import:0402-CAP")
      (libsource (lib "eagle-import") (part "CAP0402-CAP"))
    )
    (comp (ref "C59")
      (value "1n")
      (footprint "eagle-import:0402-CAP")
      (libsource (lib "eagle-import") (part "CAP0402-CAP"))
    )
    (comp (ref "C60")
      (value "330p")
      (footprint "eagle-import:0402-CAP")
      (libsource (lib "eagle-import") (part "CAP0402-CAP"))
    )
    (comp (ref "C61")
      (value "0.1u")
      (footprint "eagle-import:0402-CAP")
      (libsource (lib "eagle-import") (part "CAP0402-CAP"))
    )
    (comp (ref "C62")
      (value "0.1u")
      (footprint "eagle-import:0402-CAP")
      (libsource (lib "eagle-import") (part "CAP0402-CAP"))
    )
    (comp (ref "C63")
      (value "0.1u")
      (footprint "eagle-import:0402-CAP")
      (libsource (lib "eagle-import") (part "CAP0402-CAP"))
    )
    (comp (ref "J2")
      (value "M05X2_SMD_0.050_NOCREAM")
      (footprint "eagle-import:M05X2_0.050_SMD_NO_CREAM")
      (libsource (lib "eagle-import") (part "M05X2_SMD_0.050_NOCREAM"))
    )
    (comp (ref "R29")
      (value "18k")
      (footprint "eagle-import:0402-RES")
      (libsource (lib "eagle-import") (part "RESISTOR0402-RES"))
    )
    (comp (ref "R30")
      (value "2.2k")
      (footprint "eagle-import:0402-RES")
      (libsource (lib "eagle-import") (part "RESISTOR0402-RES"))
    )
    (comp (ref "R31")
      (value "33")
      (footprint "eagle-import:0402-RES")
      (libsource (lib "eagle-import") (part "RESISTOR0402-RES"))
    )
    (comp (ref "R32")
      (value "18k")
      (footprint "eagle-import:0402-RES")
      (libsource (lib "eagle-import") (part "RESISTOR0402-RES"))
    )
    (comp (ref "R33")
      (value "2.2k")
      (footprint "eagle-import:0402-RES")
      (libsource (lib "eagle-import") (part "RESISTOR0402-RES"))
    )
    (comp (ref "R34")
      (value "33")
      (footprint "eagle-import:0402-RES")
      (libsource (lib "eagle-import") (part "RESISTOR0402-RES"))
    )
    (comp (ref "R35")
      (value "18k")
      (footprint "eagle-import:0402-RES")
      (libsource (lib "eagle-import") (part "RESISTOR0402-RES"))
    )
    (comp (ref "R36")
      (value "2.2k")
      (footprint "eagle-import:0402-RES")
      (libsource (lib "eagle-import") (part "RESISTOR0402-RES"))
    )
    (comp (ref "R37")
      (value "33")
      (footprint "eagle-import:0402-RES")
      (libsource (lib "eagle-import") (part "RESISTOR0402-RES"))
    )
    (comp (ref "R38")
      (value "18k")
      (footprint "eagle-import:0402-RES")
      (libsource (lib "eagle-import") (part "RESISTOR0402-RES"))
    )
    (comp (ref "R39")
      (value "2.2k")
      (footprint "eagle-import:0402-RES")
      (libsource (lib "eagle-import") (part "RESISTOR0402-RES"))
    )
    (comp (ref "R40")
      (value "33")
      (footprint "eagle-import:0402-RES")
      (libsource (lib "eagle-import") (part "RESISTOR0402-RES"))
    )
    (comp (ref "R41")
      (value "18k")
      (footprint "eagle-import:0402-RES")
      (libsource (lib "eagle-import") (part "RESISTOR0402-RES"))
    )
    (comp (ref "R42")
      (value "18k")
      (footprint "eagle-import:0402-RES")
      (libsource (lib "eagle-import") (part "RESISTOR0402-RES"))
    )
    (comp (ref "TP9")
      (value "TESTPOINT_ROUND")
      (footprint "eagle-import:TESTPAD_ROUND")
      (libsource (lib "eagle-import") (part "TESTPOINT_ROUND"))
    )
    (comp (ref "TP11")
      (value "TESTPOINT_ROUND")
      (footprint "eagle-import:TESTPAD_ROUND")
      (libsource (lib "eagle-import") (part "TESTPOINT_ROUND"))
    )
    (comp (ref "TP12")
      (value "TESTPOINT_ROUND")
      (footprint "eagle-import:TESTPAD_ROUND")
      (libsource (lib "eagle-import") (part "TESTPOINT_ROUND"))
    )
    (comp (ref "U5")
      (value "AD7380")
      (footprint "eagle-import:LFCSP16")
      (libsource (lib "eagle-import") (part "AD7380"))
    )
    (comp (ref "U6")
      (value "ADA4940-2")
      (footprint "eagle-import:LFCSP24")
      (libsource (lib "eagle-import") (part "ADA4940-2"))
    )
    (comp (ref "C22")
      (value "330p")
      (footprint "eagle-import:0402-CAP")
      (libsource (lib "eagle-import") (part "CAP0402-CAP"))
    )
    (comp (ref "C23")
      (value "1n")
      (footprint "eagle-import:0402-CAP")
      (libsource (lib "eagle-import") (part "CAP0402-CAP"))
    )
    (comp (ref "C24")
      (value "1n")
      (footprint "eagle-import:0402-CAP")
      (libsource (lib "eagle-import") (part "CAP0402-CAP"))
    )
    (comp (ref "C25")
      (value "1n")
      (footprint "eagle-import:0402-CAP")
      (libsource (lib "eagle-import") (part "CAP0402-CAP"))
    )
    (comp (ref "C26")
      (value "330p")
      (footprint "eagle-import:0402-CAP")
      (libsource (lib "eagle-import") (part "CAP0402-CAP"))
    )
    (comp (ref "C27")
      (value "1u")
      (footprint "eagle-import:0402-CAP")
      (libsource (lib "eagle-import") (part "CAP0402-CAP"))
    )
    (comp (ref "C28")
      (value "1u")
      (footprint "eagle-import:0402-CAP")
      (libsource (lib "eagle-import") (part "CAP0402-CAP"))
    )
    (comp (ref "C29")
      (value "0.1u")
      (footprint "eagle-import:0402-CAP")
      (libsource (lib "eagle-import") (part "CAP0402-CAP"))
    )
    (comp (ref "C30")
      (value "0.1u")
      (footprint "eagle-import:0402-CAP")
      (libsource (lib "eagle-import") (part "CAP0402-CAP"))
    )
    (comp (ref "C31")
      (value "0.1u")
      (footprint "eagle-import:0402-CAP")
      (libsource (lib "eagle-import") (part "CAP0402-CAP"))
    )
    (comp (ref "C32")
      (value "330p")
      (footprint "eagle-import:0402-CAP")
      (libsource (lib "eagle-import") (part "CAP0402-CAP"))
    )
    (comp (ref "C33")
      (value "1u")
      (footprint "eagle-import:0402-CAP")
      (libsource (lib "eagle-import") (part "CAP0402-CAP"))
    )
    (comp (ref "C34")
      (value "0.1u")
      (footprint "eagle-import:0402-CAP")
      (libsource (lib "eagle-import") (part "CAP0402-CAP"))
    )
    (comp (ref "C35")
      (value "1u")
      (footprint "eagle-import:0402-CAP")
      (libsource (lib "eagle-import") (part "CAP0402-CAP"))
    )
    (comp (ref "C36")
      (value "1n")
      (footprint "eagle-import:0402-CAP")
      (libsource (lib "eagle-import") (part "CAP0402-CAP"))
    )
    (comp (ref "C37")
      (value "1n")
      (footprint "eagle-import:0402-CAP")
      (libsource (lib "eagle-import") (part "CAP0402-CAP"))
    )
    (comp (ref "C38")
      (value "1n")
      (footprint "eagle-import:0402-CAP")
      (libsource (lib "eagle-import") (part "CAP0402-CAP"))
    )
    (comp (ref "C39")
      (value "330p")
      (footprint "eagle-import:0402-CAP")
      (libsource (lib "eagle-import") (part "CAP0402-CAP"))
    )
    (comp (ref "C40")
      (value "0.1u")
      (footprint "eagle-import:0402-CAP")
      (libsource (lib "eagle-import") (part "CAP0402-CAP"))
    )
    (comp (ref "C41")
      (value "0.1u")
      (footprint "eagle-import:0402-CAP")
      (libsource (lib "eagle-import") (part "CAP0402-CAP"))
    )
    (comp (ref "C42")
      (value "0.1u")
      (footprint "eagle-import:0402-CAP")
      (libsource (lib "eagle-import") (part "CAP0402-CAP"))
    )
    (comp (ref "R15")
      (value "18k")
      (footprint "eagle-import:0402-RES")
      (libsource (lib "eagle-import") (part "RESISTOR0402-RES"))
    )
    (comp (ref "R16")
      (value "2.2k")
      (footprint "eagle-import:0402-RES")
      (libsource (lib "eagle-import") (part "RESISTOR0402-RES"))
    )
    (comp (ref "R17")
      (value "33")
      (footprint "eagle-import:0402-RES")
      (libsource (lib "eagle-import") (part "RESISTOR0402-RES"))
    )
    (comp (ref "R18")
      (value "18k")
      (footprint "eagle-import:0402-RES")
      (libsource (lib "eagle-import") (part "RESISTOR0402-RES"))
    )
    (comp (ref "R19")
      (value "2.2k")
      (footprint "eagle-import:0402-RES")
      (libsource (lib "eagle-import") (part "RESISTOR0402-RES"))
    )
    (comp (ref "R20")
      (value "33")
      (footprint "eagle-import:0402-RES")
      (libsource (lib "eagle-import") (part "RESISTOR0402-RES"))
    )
    (comp (ref "R21")
      (value "18k")
      (footprint "eagle-import:0402-RES")
      (libsource (lib "eagle-import") (part "RESISTOR0402-RES"))
    )
    (comp (ref "R22")
      (value "2.2k")
      (footprint "eagle-import:0402-RES")
      (libsource (lib "eagle-import") (part "RESISTOR0402-RES"))
    )
    (comp (ref "R23")
      (value "33")
      (footprint "eagle-import:0402-RES")
      (libsource (lib "eagle-import") (part "RESISTOR0402-RES"))
    )
    (comp (ref "R24")
      (value "18k")
      (footprint "eagle-import:0402-RES")
      (libsource (lib "eagle-import") (part "RESISTOR0402-RES"))
    )
    (comp (ref "R25")
      (value "2.2k")
      (footprint "eagle-import:0402-RES")
      (libsource (lib "eagle-import") (part "RESISTOR0402-RES"))
    )
    (comp (ref "R26")
      (value "33")
      (footprint "eagle-import:0402-RES")
      (libsource (lib "eagle-import") (part "RESISTOR0402-RES"))
    )
    (comp (ref "R27")
      (value "18k")
      (footprint "eagle-import:0402-RES")
      (libsource (lib "eagle-import") (part "RESISTOR0402-RES"))
    )
    (comp (ref "R28")
      (value "18k")
      (footprint "eagle-import:0402-RES")
      (libsource (lib "eagle-import") (part "RESISTOR0402-RES"))
    )
    (comp (ref "TP6")
      (value "TESTPOINT_ROUND")
      (footprint "eagle-import:TESTPAD_ROUND")
      (libsource (lib "eagle-import") (part "TESTPOINT_ROUND"))
    )
    (comp (ref "TP7")
      (value "TESTPOINT_ROUND")
      (footprint "eagle-import:TESTPAD_ROUND")
      (libsource (lib "eagle-import") (part "TESTPOINT_ROUND"))
    )
    (comp (ref "TP8")
      (value "TESTPOINT_ROUND")
      (footprint "eagle-import:TESTPAD_ROUND")
      (libsource (lib "eagle-import") (part "TESTPOINT_ROUND"))
    )
    (comp (ref "U3")
      (value "AD7380")
      (footprint "eagle-import:LFCSP16")
      (libsource (lib "eagle-import") (part "AD7380"))
    )
    (comp (ref "U4")
      (value "ADA4940-2")
      (footprint "eagle-import:LFCSP24")
      (libsource (lib "eagle-import") (part "ADA4940-2"))
    )
  )
  (nets
    (net (code "1") (name "A_COMM") (class "Default")
      (node (ref "J1") (pin "33") (pinfunction "33_33") (pintype "passive"))
      (node (ref "R63") (pin "2") (pinfunction "2_2") (pintype "passive"))
    )
    (net (code "2") (name "BOOTSEL") (class "Default")
      (node (ref "J5") (pin "B17") (pinfunction "33_B17") (pintype "passive"))
      (node (ref "R57") (pin "1") (pinfunction "1_1") (pintype "passive"))
      (node (ref "S1") (pin "4") (pinfunction "2_4") (pintype "passive"))
    )
    (net (code "3") (name "DET0") (class "Default")
      (node (ref "J1") (pin "4") (pinfunction "4_4") (pintype "passive"))
      (node (ref "R7") (pin "1") (pinfunction "1_1") (pintype "passive"))
      (node (ref "TP4") (pin "P$1") (pinfunction "P$1_P$1") (pintype "bidirectional"))
    )
    (net (code "4") (name "DET1") (class "Default")
      (node (ref "J1") (pin "8") (pinfunction "8_8") (pintype "passive"))
      (node (ref "R1") (pin "1") (pinfunction "1_1") (pintype "passive"))
      (node (ref "TP1") (pin "P$1") (pinfunction "P$1_P$1") (pintype "bidirectional"))
    )
    (net (code "5") (name "DET2") (class "Default")
      (node (ref "J1") (pin "12") (pinfunction "12_12") (pintype "passive"))
      (node (ref "R29") (pin "1") (pinfunction "1_1") (pintype "passive"))
      (node (ref "TP9") (pin "P$1") (pinfunction "P$1_P$1") (pintype "bidirectional"))
    )
    (net (code "6") (name "DET3") (class "Default")
      (node (ref "J1") (pin "16") (pinfunction "16_16") (pintype "passive"))
      (node (ref "R35") (pin "1") (pinfunction "1_1") (pintype "passive"))
      (node (ref "TP11") (pin "P$1") (pinfunction "P$1_P$1") (pintype "bidirectional"))
    )
    (net (code "7") (name "DET4") (class "Default")
      (node (ref "J1") (pin "20") (pinfunction "20_20") (pintype "passive"))
      (node (ref "R21") (pin "1") (pinfunction "1_1") (pintype "passive"))
      (node (ref "TP7") (pin "P$1") (pinfunction "P$1_P$1") (pintype "bidirectional"))
    )
    (net (code "8") (name "DET5") (class "Default")
      (node (ref "J1") (pin "24") (pinfunction "24_24") (pintype "passive"))
      (node (ref "R15") (pin "1") (pinfunction "1_1") (pintype "passive"))
      (node (ref "TP6") (pin "P$1") (pinfunction "P$1_P$1") (pintype "bidirectional"))
    )
    (net (code "9") (name "DET6") (class "Default")
      (node (ref "J1") (pin "28") (pinfunction "28_28") (pintype "passive"))
      (node (ref "R43") (pin "1") (pinfunction "1_1") (pintype "passive"))
      (node (ref "TP13") (pin "P$1") (pinfunction "P$1_P$1") (pintype "bidirectional"))
    )
    (net (code "10") (name "DET7") (class "Default")
      (node (ref "J1") (pin "32") (pinfunction "32_32") (pintype "passive"))
      (node (ref "R49") (pin "1") (pinfunction "1_1") (pintype "passive"))
      (node (ref "TP15") (pin "P$1") (pinfunction "P$1_P$1") (pintype "bidirectional"))
    )
    (net (code "11") (name "GND") (class "Default")
      (node (ref "C10") (pin "2") (pinfunction "2_2") (pintype "passive"))
      (node (ref "C100") (pin "2") (pinfunction "2_2") (pintype "passive"))
      (node (ref "C101") (pin "2") (pinfunction "2_2") (pintype "passive"))
      (node (ref "C102") (pin "2") (pinfunction "2_2") (pintype "passive"))
      (node (ref "C103") (pin "2") (pinfunction "2_2") (pintype "passive"))
      (node (ref "C104") (pin "2") (pinfunction "2_2") (pintype "passive"))
      (node (ref "C105") (pin "2") (pinfunction "2_2") (pintype "passive"))
      (node (ref "C106") (pin "1") (pinfunction "1_1") (pintype "passive"))
      (node (ref "C107") (pin "1") (pinfunction "1_1") (pintype "passive"))
      (node (ref "C108") (pin "1") (pinfunction "1_1") (pintype "passive"))
      (node (ref "C109") (pin "1") (pinfunction "1_1") (pintype "passive"))
      (node (ref "C111") (pin "2") (pinfunction "2_2") (pintype "passive"))
      (node (ref "C112") (pin "1") (pinfunction "1_1") (pintype "passive"))
      (node (ref "C113") (pin "2") (pinfunction "2_2") (pintype "passive"))
      (node (ref "C12") (pin "2") (pinfunction "2_2") (pintype "passive"))
      (node (ref "C13") (pin "2") (pinfunction "2_2") (pintype "passive"))
      (node (ref "C14") (pin "2") (pinfunction "2_2") (pintype "passive"))
      (node (ref "C15") (pin "1") (pinfunction "1_1") (pintype "passive"))
      (node (ref "C17") (pin "2") (pinfunction "2_2") (pintype "passive"))
      (node (ref "C19") (pin "2") (pinfunction "2_2") (pintype "passive"))
      (node (ref "C2") (pin "1") (pinfunction "1_1") (pintype "passive"))
      (node (ref "C20") (pin "2") (pinfunction "2_2") (pintype "passive"))
      (node (ref "C21") (pin "2") (pinfunction "2_2") (pintype "passive"))
      (node (ref "C23") (pin "1") (pinfunction "1_1") (pintype "passive"))
      (node (ref "C25") (pin "2") (pinfunction "2_2") (pintype "passive"))
      (node (ref "C27") (pin "2") (pinfunction "2_2") (pintype "passive"))
      (node (ref "C28") (pin "2") (pinfunction "2_2") (pintype "passive"))
      (node (ref "C29") (pin "2") (pinfunction "2_2") (pintype "passive"))
      (node (ref "C30") (pin "2") (pinfunction "2_2") (pintype "passive"))
      (node (ref "C31") (pin "2") (pinfunction "2_2") (pintype "passive"))
      (node (ref "C33") (pin "2") (pinfunction "2_2") (pintype "passive"))
      (node (ref "C34") (pin "2") (pinfunction "2_2") (pintype "passive"))
      (node (ref "C35") (pin "2") (pinfunction "2_2") (pintype "passive"))
      (node (ref "C36") (pin "1") (pinfunction "1_1") (pintype "passive"))
      (node (ref "C38") (pin "2") (pinfunction "2_2") (pintype "passive"))
      (node (ref "C4") (pin "2") (pinfunction "2_2") (pintype "passive"))
      (node (ref "C40") (pin "2") (pinfunction "2_2") (pintype "passive"))
      (node (ref "C41") (pin "2") (pinfunction "2_2") (pintype "passive"))
      (node (ref "C42") (pin "2") (pinfunction "2_2") (pintype "passive"))
      (node (ref "C44") (pin "1") (pinfunction "1_1") (pintype "passive"))
      (node (ref "C46") (pin "2") (pinfunction "2_2") (pintype "passive"))
      (node (ref "C48") (pin "2") (pinfunction "2_2") (pintype "passive"))
      (node (ref "C49") (pin "2") (pinfunction "2_2") (pintype "passive"))
      (node (ref "C50") (pin "2") (pinfunction "2_2") (pintype "passive"))
      (node (ref "C51") (pin "2") (pinfunction "2_2") (pintype "passive"))
      (node (ref "C52") (pin "2") (pinfunction "2_2") (pintype "passive"))
      (node (ref "C54") (pin "2") (pinfunction "2_2") (pintype "passive"))
      (node (ref "C55") (pin "2") (pinfunction "2_2") (pintype "passive"))
      (node (ref "C56") (pin "2") (pinfunction "2_2") (pintype "passive"))
      (node (ref "C57") (pin "1") (pinfunction "1_1") (pintype "passive"))
      (node (ref "C59") (pin "2") (pinfunction "2_2") (pintype "passive"))
      (node (ref "C6") (pin "2") (pinfunction "2_2") (pintype "passive"))
      (node (ref "C61") (pin "2") (pinfunction "2_2") (pintype "passive"))
      (node (ref "C62") (pin "2") (pinfunction "2_2") (pintype "passive"))
      (node (ref "C63") (pin "2") (pinfunction "2_2") (pintype "passive"))
      (node (ref "C65") (pin "1") (pinfunction "1_1") (pintype "passive"))
      (node (ref "C67") (pin "2") (pinfunction "2_2") (pintype "passive"))
      (node (ref "C69") (pin "2") (pinfunction "2_2") (pintype "passive"))
      (node (ref "C7") (pin "2") (pinfunction "2_2") (pintype "passive"))
      (node (ref "C70") (pin "2") (pinfunction "2_2") (pintype "passive"))
      (node (ref "C71") (pin "2") (pinfunction "2_2") (pintype "passive"))
      (node (ref "C72") (pin "2") (pinfunction "2_2") (pintype "passive"))
      (node (ref "C73") (pin "2") (pinfunction "2_2") (pintype "passive"))
      (node (ref "C75") (pin "2") (pinfunction "2_2") (pintype "passive"))
      (node (ref "C76") (pin "2") (pinfunction "2_2") (pintype "passive"))
      (node (ref "C77") (pin "2") (pinfunction "2_2") (pintype "passive"))
      (node (ref "C78") (pin "1") (pinfunction "1_1") (pintype "passive"))
      (node (ref "C8") (pin "2") (pinfunction "2_2") (pintype "passive"))
      (node (ref "C80") (pin "2") (pinfunction "2_2") (pintype "passive"))
      (node (ref "C82") (pin "2") (pinfunction "2_2") (pintype "passive"))
      (node (ref "C83") (pin "2") (pinfunction "2_2") (pintype "passive"))
      (node (ref "C84") (pin "2") (pinfunction "2_2") (pintype "passive"))
      (node (ref "C85") (pin "2") (pinfunction "2_2") (pintype "passive"))
      (node (ref "C86") (pin "2") (pinfunction "2_2") (pintype "passive"))
      (node (ref "C87") (pin "2") (pinfunction "2_2") (pintype "passive"))
      (node (ref "C88") (pin "2") (pinfunction "2_2") (pintype "passive"))
      (node (ref "C89") (pin "2") (pinfunction "2_2") (pintype "passive"))
      (node (ref "C9") (pin "2") (pinfunction "2_2") (pintype "passive"))
      (node (ref "C90") (pin "2") (pinfunction "2_2") (pintype "passive"))
      (node (ref "C91") (pin "2") (pinfunction "2_2") (pintype "passive"))
      (node (ref "C92") (pin "2") (pinfunction "2_2") (pintype "passive"))
      (node (ref "C93") (pin "2") (pinfunction "2_2") (pintype "passive"))
      (node (ref "C94") (pin "2") (pinfunction "2_2") (pintype "passive"))
      (node (ref "C95") (pin "2") (pinfunction "2_2") (pintype "passive"))
      (node (ref "C96") (pin "2") (pinfunction "2_2") (pintype "passive"))
      (node (ref "C97") (pin "2") (pinfunction "2_2") (pintype "passive"))
      (node (ref "C98") (pin "2") (pinfunction "2_2") (pintype "passive"))
      (node (ref "C99") (pin "2") (pinfunction "2_2") (pintype "passive"))
      (node (ref "J1") (pin "11") (pinfunction "11_11") (pintype "passive"))
      (node (ref "J1") (pin "15") (pinfunction "15_15") (pintype "passive"))
      (node (ref "J1") (pin "19") (pinfunction "19_19") (pintype "passive"))
      (node (ref "J1") (pin "23") (pinfunction "23_23") (pintype "passive"))
      (node (ref "J1") (pin "27") (pinfunction "27_27") (pintype "passive"))
      (node (ref "J1") (pin "3") (pinfunction "3_3") (pintype "passive"))
      (node (ref "J1") (pin "31") (pinfunction "31_31") (pintype "passive"))
      (node (ref "J1") (pin "7") (pinfunction "7_7") (pintype "passive"))
      (node (ref "J2") (pin "1") (pinfunction "1_1") (pintype "passive"))
      (node (ref "J2") (pin "3") (pinfunction "3_3") (pintype "passive"))
      (node (ref "J2") (pin "5") (pinfunction "5_5") (pintype "passive"))
      (node (ref "J2") (pin "7") (pinfunction "7_7") (pintype "passive"))
      (node (ref "J2") (pin "9") (pinfunction "9_9") (pintype "passive"))
      (node (ref "J3") (pin "2") (pinfunction "2_2") (pintype "passive"))
      (node (ref "J4") (pin "5") (pinfunction "5_5") (pintype "bidirectional"))
      (node (ref "J4") (pin "SH1") (pinfunction "SH1_SH1") (pintype "bidirectional"))
      (node (ref "J4") (pin "SH2") (pinfunction "SH2_SH2") (pintype "bidirectional"))
      (node (ref "J4") (pin "SH3") (pinfunction "SH3_SH3") (pintype "bidirectional"))
      (node (ref "J4") (pin "SH4") (pinfunction "SH4_SH4") (pintype "bidirectional"))
      (node (ref "J4") (pin "SH5") (pinfunction "SH5_SH5") (pintype "bidirectional"))
      (node (ref "J4") (pin "SH6") (pinfunction "SH6_SH6") (pintype "bidirectional"))
      (node (ref "J5") (pin "A10") (pinfunction "20_A10") (pintype "passive"))
      (node (ref "J5") (pin "A11") (pinfunction "22_A11") (pintype "passive"))
      (node (ref "J5") (pin "A12") (pinfunction "24_A12") (pintype "passive"))
      (node (ref "J5") (pin "A13") (pinfunction "26_A13") (pintype "passive"))
      (node (ref "J5") (pin "A14") (pinfunction "28_A14") (pintype "passive"))
      (node (ref "J5") (pin "A15") (pinfunction "30_A15") (pintype "passive"))
      (node (ref "J5") (pin "A16") (pinfunction "32_A16") (pintype "passive"))
      (node (ref "J5") (pin "A17") (pinfunction "34_A17") (pintype "passive"))
      (node (ref "J5") (pin "A2") (pinfunction "4_A2") (pintype "passive"))
      (node (ref "J5") (pin "A20") (pinfunction "40_A20") (pintype "passive"))
      (node (ref "J5") (pin "A4") (pinfunction "8_A4") (pintype "passive"))
      (node (ref "J5") (pin "A5") (pinfunction "10_A5") (pintype "passive"))
      (node (ref "J5") (pin "A6") (pinfunction "12_A6") (pintype "passive"))
      (node (ref "J5") (pin "A7") (pinfunction "14_A7") (pintype "passive"))
      (node (ref "J5") (pin "A8") (pinfunction "16_A8") (pintype "passive"))
      (node (ref "J5") (pin "A9") (pinfunction "18_A9") (pintype "passive"))
      (node (ref "J5") (pin "B18") (pinfunction "35_B18") (pintype "passive"))
      (node (ref "J5") (pin "B19") (pinfunction "37_B19") (pintype "passive"))
      (node (ref "J5") (pin "B2") (pinfunction "3_B2") (pintype "passive"))
      (node (ref "J5") (pin "B4") (pinfunction "7_B4") (pintype "passive"))
      (node (ref "J5") (pin "B8") (pinfunction "15_B8") (pintype "passive"))
      (node (ref "LED1") (pin "C") (pinfunction "C_C") (pintype "passive"))
      (node (ref "R10") (pin "1") (pinfunction "1_1") (pintype "passive"))
      (node (ref "R14") (pin "1") (pinfunction "1_1") (pintype "passive"))
      (node (ref "R18") (pin "1") (pinfunction "1_1") (pintype "passive"))
      (node (ref "R24") (pin "1") (pinfunction "1_1") (pintype "passive"))
      (node (ref "R28") (pin "1") (pinfunction "1_1") (pintype "passive"))
      (node (ref "R32") (pin "1") (pinfunction "1_1") (pintype "passive"))
      (node (ref "R38") (pin "1") (pinfunction "1_1") (pintype "passive"))
      (node (ref "R4") (pin "1") (pinfunction "1_1") (pintype "passive"))
      (node (ref "R42") (pin "1") (pinfunction "1_1") (pintype "passive"))
      (node (ref "R46") (pin "1") (pinfunction "1_1") (pintype "passive"))
      (node (ref "R52") (pin "1") (pinfunction "1_1") (pintype "passive"))
      (node (ref "R56") (pin "1") (pinfunction "1_1") (pintype "passive"))
      (node (ref "R67") (pin "1") (pinfunction "1_1") (pintype "passive"))
      (node (ref "R68") (pin "2") (pinfunction "2_2") (pintype "passive"))
      (node (ref "S1") (pin "1") (pinfunction "1_1") (pintype "passive"))
      (node (ref "TP20") (pin "1") (pinfunction "P$1_1") (pintype "bidirectional"))
      (node (ref "U1") (pin "1") (pinfunction "GND_1") (pintype "power_in"))
      (node (ref "U1") (pin "10") (pinfunction "GND_10") (pintype "power_in"))
      (node (ref "U1") (pin "EP") (pinfunction "GND_EP") (pintype "power_in"))
      (node (ref "U10") (pin "19") (pinfunction "TESTEN_19") (pintype "input"))
      (node (ref "U10") (pin "PAD") (pinfunction "GND_PAD") (pintype "power_in"))
      (node (ref "U11") (pin "4") (pinfunction "GND_4") (pintype "power_in"))
      (node (ref "U11") (pin "P") (pinfunction "GND_P") (pintype "power_in"))
      (node (ref "U12") (pin "4") (pinfunction "GND_4") (pintype "power_in"))
      (node (ref "U12") (pin "P") (pinfunction "GND_P") (pintype "power_in"))
      (node (ref "U13") (pin "3") (pinfunction "GND_3") (pintype "power_in"))
      (node (ref "U13") (pin "PAD") (pinfunction "GND_PAD") (pintype "power_in"))
      (node (ref "U14") (pin "5") (pinfunction "GND_5") (pintype "bidirectional"))
      (node (ref "U15") (pin "5") (pinfunction "GND_5") (pintype "bidirectional"))
      (node (ref "U2") (pin "EP") (pinfunction "1_EP") (pintype "passive"))
      (node (ref "U3") (pin "1") (pinfunction "GND_1") (pintype "power_in"))
      (node (ref "U3") (pin "10") (pinfunction "GND_10") (pintype "power_in"))
      (node (ref "U3") (pin "EP") (pinfunction "GND_EP") (pintype "power_in"))
      (node (ref "U4") (pin "EP") (pinfunction "1_EP") (pintype "passive"))
      (node (ref "U5") (pin "1") (pinfunction "GND_1") (pintype "power_in"))
      (node (ref "U5") (pin "10") (pinfunction "GND_10") (pintype "power_in"))
      (node (ref "U5") (pin "EP") (pinfunction "GND_EP") (pintype "power_in"))
      (node (ref "U6") (pin "EP") (pinfunction "1_EP") (pintype "passive"))
      (node (ref "U7") (pin "1") (pinfunction "GND_1") (pintype "power_in"))
      (node (ref "U7") (pin "10") (pinfunction "GND_10") (pintype "power_in"))
      (node (ref "U7") (pin "EP") (pinfunction "GND_EP") (pintype "power_in"))
      (node (ref "U8") (pin "EP") (pinfunction "1_EP") (pintype "passive"))
      (node (ref "U9") (pin "4") (pinfunction "GND_4") (pintype "power_in"))
      (node (ref "X1") (pin "2") (pinfunction "GND_2") (pintype "passive"))
      (node (ref "X1") (pin "4") (pinfunction "GND_4") (pintype "passive"))
    )
    (net (code "12") (name "GPIO00") (class "Default")
      (node (ref "J5") (pin "B15") (pinfunction "29_B15") (pintype "passive"))
      (node (ref "U10") (pin "2") (pinfunction "GPIO00_2") (pintype "bidirectional"))
    )
    (net (code "13") (name "GPIO01") (class "Default")
      (node (ref "J5") (pin "B14") (pinfunction "27_B14") (pintype "passive"))
      (node (ref "U10") (pin "3") (pinfunction "GPIO01_3") (pintype "bidirectional"))
    )
    (net (code "14") (name "GPIO02") (class "Default")
      (node (ref "J5") (pin "B13") (pinfunction "25_B13") (pintype "passive"))
      (node (ref "U10") (pin "4") (pinfunction "GPIO02_4") (pintype "bidirectional"))
    )
    (net (code "15") (name "GPIO03") (class "Default")
      (node (ref "J5") (pin "B12") (pinfunction "23_B12") (pintype "passive"))
      (node (ref "U10") (pin "5") (pinfunction "GPIO03_5") (pintype "bidirectional"))
    )
    (net (code "16") (name "GPIO04") (class "Default")
      (node (ref "J5") (pin "B11") (pinfunction "21_B11") (pintype "passive"))
      (node (ref "U10") (pin "6") (pinfunction "GPIO04_6") (pintype "bidirectional"))
    )
    (net (code "17") (name "GPIO05") (class "Default")
      (node (ref "J5") (pin "B10") (pinfunction "19_B10") (pintype "passive"))
      (node (ref "U10") (pin "7") (pinfunction "GPIO05_7") (pintype "bidirectional"))
    )
    (net (code "18") (name "GPIO06") (class "Default")
      (node (ref "J5") (pin "B9") (pinfunction "17_B9") (pintype "passive"))
      (node (ref "U10") (pin "8") (pinfunction "GPIO06_8") (pintype "bidirectional"))
    )
    (net (code "19") (name "LED") (class "Default")
      (node (ref "R62") (pin "2") (pinfunction "2_2") (pintype "passive"))
      (node (ref "R63") (pin "1") (pinfunction "1_1") (pintype "passive"))
      (node (ref "U10") (pin "9") (pinfunction "GPIO07_9") (pintype "bidirectional"))
    )
    (net (code "20") (name "Net-(C110-Pad1)") (class "Default")
      (node (ref "C110") (pin "1") (pinfunction "1_1") (pintype "passive"))
      (node (ref "R70") (pin "1") (pinfunction "1_1") (pintype "passive"))
    )
    (net (code "21") (name "Net-(J4-Pad2)") (class "Default")
      (node (ref "J4") (pin "2") (pinfunction "2_2") (pintype "bidirectional"))
      (node (ref "R61") (pin "2") (pinfunction "2_2") (pintype "passive"))
    )
    (net (code "22") (name "Net-(J4-Pad3)") (class "Default")
      (node (ref "J4") (pin "3") (pinfunction "3_3") (pintype "bidirectional"))
      (node (ref "R60") (pin "2") (pinfunction "2_2") (pintype "passive"))
    )
    (net (code "23") (name "Net-(LED1-PadA)") (class "Default")
      (node (ref "LED1") (pin "A") (pinfunction "A_A") (pintype "passive"))
      (node (ref "R62") (pin "1") (pinfunction "1_1") (pintype "passive"))
    )
    (net (code "24") (name "Net-(LF1-P$1)") (class "Default")
      (node (ref "J1") (pin "1") (pinfunction "1_1") (pintype "passive"))
      (node (ref "J1") (pin "13") (pinfunction "13_13") (pintype "passive"))
      (node (ref "J1") (pin "17") (pinfunction "17_17") (pintype "passive"))
      (node (ref "J1") (pin "21") (pinfunction "21_21") (pintype "passive"))
      (node (ref "J1") (pin "25") (pinfunction "25_25") (pintype "passive"))
      (node (ref "J1") (pin "29") (pinfunction "29_29") (pintype "passive"))
      (node (ref "J1") (pin "5") (pinfunction "5_5") (pintype "passive"))
      (node (ref "J1") (pin "9") (pinfunction "9_9") (pintype "passive"))
      (node (ref "LF1") (pin "1") (pinfunction "P$1_1") (pintype "bidirectional"))
      (node (ref "R71") (pin "1") (pinfunction "1_1") (pintype "passive"))
      (node (ref "TP2") (pin "P$1") (pinfunction "P$1_P$1") (pintype "bidirectional"))
    )
    (net (code "25") (name "Net-(LF2-P$1)") (class "Default")
      (node (ref "J1") (pin "10") (pinfunction "10_10") (pintype "passive"))
      (node (ref "J1") (pin "14") (pinfunction "14_14") (pintype "passive"))
      (node (ref "J1") (pin "18") (pinfunction "18_18") (pintype "passive"))
      (node (ref "J1") (pin "2") (pinfunction "2_2") (pintype "passive"))
      (node (ref "J1") (pin "22") (pinfunction "22_22") (pintype "passive"))
      (node (ref "J1") (pin "26") (pinfunction "26_26") (pintype "passive"))
      (node (ref "J1") (pin "30") (pinfunction "30_30") (pintype "passive"))
      (node (ref "J1") (pin "6") (pinfunction "6_6") (pintype "passive"))
      (node (ref "LF2") (pin "1") (pinfunction "P$1_1") (pintype "bidirectional"))
      (node (ref "TP3") (pin "P$1") (pinfunction "P$1_P$1") (pintype "bidirectional"))
    )
    (net (code "26") (name "Net-(U1-AINA+)") (class "Default")
      (node (ref "C3") (pin "2") (pinfunction "2_2") (pintype "passive"))
      (node (ref "C4") (pin "1") (pinfunction "1_1") (pintype "passive"))
      (node (ref "R6") (pin "2") (pinfunction "2_2") (pintype "passive"))
      (node (ref "U1") (pin "8") (pinfunction "AINA+_8") (pintype "input"))
    )
    (net (code "27") (name "Net-(U1-AINA-)") (class "Default")
      (node (ref "C2") (pin "2") (pinfunction "2_2") (pintype "passive"))
      (node (ref "C3") (pin "1") (pinfunction "1_1") (pintype "passive"))
      (node (ref "R3") (pin "2") (pinfunction "2_2") (pintype "passive"))
      (node (ref "U1") (pin "7") (pinfunction "AINA-_7") (pintype "input"))
    )
    (net (code "28") (name "Net-(U1-AINB+)") (class "Default")
      (node (ref "C16") (pin "2") (pinfunction "2_2") (pintype "passive"))
      (node (ref "C17") (pin "1") (pinfunction "1_1") (pintype "passive"))
      (node (ref "R12") (pin "2") (pinfunction "2_2") (pintype "passive"))
      (node (ref "U1") (pin "6") (pinfunction "AINB+_6") (pintype "input"))
    )
    (net (code "29") (name "Net-(U1-AINB-)") (class "Default")
      (node (ref "C15") (pin "2") (pinfunction "2_2") (pintype "passive"))
      (node (ref "C16") (pin "1") (pinfunction "1_1") (pintype "passive"))
      (node (ref "R9") (pin "2") (pinfunction "2_2") (pintype "passive"))
      (node (ref "U1") (pin "5") (pinfunction "AINB-_5") (pintype "input"))
    )
    (net (code "30") (name "Net-(U1-REFCAP)") (class "Default")
      (node (ref "C13") (pin "1") (pinfunction "1_1") (pintype "passive"))
      (node (ref "U1") (pin "9") (pinfunction "REFCAP_9") (pintype "bidirectional"))
    )
    (net (code "31") (name "Net-(U1-REFIO)") (class "Default")
      (node (ref "C12") (pin "1") (pinfunction "1_1") (pintype "passive"))
      (node (ref "R13") (pin "2") (pinfunction "2_2") (pintype "passive"))
      (node (ref "U1") (pin "11") (pinfunction "REFIO_11") (pintype "bidirectional"))
    )
    (net (code "32") (name "Net-(U1-REGCAP)") (class "Default")
      (node (ref "C14") (pin "1") (pinfunction "1_1") (pintype "passive"))
      (node (ref "U1") (pin "3") (pinfunction "REGCAP_3") (pintype "bidirectional"))
    )
    (net (code "33") (name "Net-(U2A-+FB)") (class "Default")
      (node (ref "C18") (pin "2") (pinfunction "2_2") (pintype "passive"))
      (node (ref "R11") (pin "2") (pinfunction "2_2") (pintype "passive"))
      (node (ref "U2") (pin "2") (pinfunction "+FB_2") (pintype "output"))
    )
    (net (code "34") (name "Net-(U2A-+IN)") (class "Default")
      (node (ref "C11") (pin "1") (pinfunction "1_1") (pintype "passive"))
      (node (ref "R7") (pin "2") (pinfunction "2_2") (pintype "passive"))
      (node (ref "R8") (pin "1") (pinfunction "1_1") (pintype "passive"))
      (node (ref "U2") (pin "24") (pinfunction "+IN_24") (pintype "input"))
    )
    (net (code "35") (name "Net-(U2A-+OUT)") (class "Default")
      (node (ref "R12") (pin "1") (pinfunction "1_1") (pintype "passive"))
      (node (ref "U2") (pin "18") (pinfunction "+OUT_18") (pintype "output"))
    )
    (net (code "36") (name "Net-(U2A--FB)") (class "Default")
      (node (ref "C11") (pin "2") (pinfunction "2_2") (pintype "passive"))
      (node (ref "R8") (pin "2") (pinfunction "2_2") (pintype "passive"))
      (node (ref "U2") (pin "23") (pinfunction "-FB_23") (pintype "output"))
    )
    (net (code "37") (name "Net-(U2A--IN)") (class "Default")
      (node (ref "C18") (pin "1") (pinfunction "1_1") (pintype "passive"))
      (node (ref "R10") (pin "2") (pinfunction "2_2") (pintype "passive"))
      (node (ref "R11") (pin "1") (pinfunction "1_1") (pintype "passive"))
      (node (ref "U2") (pin "1") (pinfunction "-IN_1") (pintype "input"))
    )
    (net (code "38") (name "Net-(U2A--OUT)") (class "Default")
      (node (ref "R9") (pin "1") (pinfunction "1_1") (pintype "passive"))
      (node (ref "U2") (pin "19") (pinfunction "-OUT_19") (pintype "output"))
    )
    (net (code "39") (name "Net-(U2B-+FB)") (class "Default")
      (node (ref "C5") (pin "2") (pinfunction "2_2") (pintype "passive"))
      (node (ref "R5") (pin "2") (pinfunction "2_2") (pintype "passive"))
      (node (ref "U2") (pin "8") (pinfunction "+FB_8") (pintype "output"))
    )
    (net (code "40") (name "Net-(U2B-+IN)") (class "Default")
      (node (ref "C1") (pin "1") (pinfunction "1_1") (pintype "passive"))
      (node (ref "R1") (pin "2") (pinfunction "2_2") (pintype "passive"))
      (node (ref "R2") (pin "1") (pinfunction "1_1") (pintype "passive"))
      (node (ref "U2") (pin "6") (pinfunction "+IN_6") (pintype "input"))
    )
    (net (code "41") (name "Net-(U2B-+OUT)") (class "Default")
      (node (ref "R6") (pin "1") (pinfunction "1_1") (pintype "passive"))
      (node (ref "U2") (pin "12") (pinfunction "+OUT_12") (pintype "output"))
    )
    (net (code "42") (name "Net-(U2B--FB)") (class "Default")
      (node (ref "C1") (pin "2") (pinfunction "2_2") (pintype "passive"))
      (node (ref "R2") (pin "2") (pinfunction "2_2") (pintype "passive"))
      (node (ref "U2") (pin "5") (pinfunction "-FB_5") (pintype "output"))
    )
    (net (code "43") (name "Net-(U2B--IN)") (class "Default")
      (node (ref "C5") (pin "1") (pinfunction "1_1") (pintype "passive"))
      (node (ref "R4") (pin "2") (pinfunction "2_2") (pintype "passive"))
      (node (ref "R5") (pin "1") (pinfunction "1_1") (pintype "passive"))
      (node (ref "U2") (pin "7") (pinfunction "-IN_7") (pintype "input"))
    )
    (net (code "44") (name "Net-(U2B--OUT)") (class "Default")
      (node (ref "R3") (pin "1") (pinfunction "1_1") (pintype "passive"))
      (node (ref "U2") (pin "13") (pinfunction "-OUT_13") (pintype "output"))
    )
    (net (code "45") (name "Net-(U3-AINA+)") (class "Default")
      (node (ref "C24") (pin "2") (pinfunction "2_2") (pintype "passive"))
      (node (ref "C25") (pin "1") (pinfunction "1_1") (pintype "passive"))
      (node (ref "R20") (pin "2") (pinfunction "2_2") (pintype "passive"))
      (node (ref "U3") (pin "8") (pinfunction "AINA+_8") (pintype "input"))
    )
    (net (code "46") (name "Net-(U3-AINA-)") (class "Default")
      (node (ref "C23") (pin "2") (pinfunction "2_2") (pintype "passive"))
      (node (ref "C24") (pin "1") (pinfunction "1_1") (pintype "passive"))
      (node (ref "R17") (pin "2") (pinfunction "2_2") (pintype "passive"))
      (node (ref "U3") (pin "7") (pinfunction "AINA-_7") (pintype "input"))
    )
    (net (code "47") (name "Net-(U3-AINB+)") (class "Default")
      (node (ref "C37") (pin "2") (pinfunction "2_2") (pintype "passive"))
      (node (ref "C38") (pin "1") (pinfunction "1_1") (pintype "passive"))
      (node (ref "R26") (pin "2") (pinfunction "2_2") (pintype "passive"))
      (node (ref "U3") (pin "6") (pinfunction "AINB+_6") (pintype "input"))
    )
    (net (code "48") (name "Net-(U3-AINB-)") (class "Default")
      (node (ref "C36") (pin "2") (pinfunction "2_2") (pintype "passive"))
      (node (ref "C37") (pin "1") (pinfunction "1_1") (pintype "passive"))
      (node (ref "R23") (pin "2") (pinfunction "2_2") (pintype "passive"))
      (node (ref "U3") (pin "5") (pinfunction "AINB-_5") (pintype "input"))
    )
    (net (code "49") (name "Net-(U3-REFCAP)") (class "Default")
      (node (ref "C34") (pin "1") (pinfunction "1_1") (pintype "passive"))
      (node (ref "U3") (pin "9") (pinfunction "REFCAP_9") (pintype "bidirectional"))
    )
    (net (code "50") (name "Net-(U3-REFIO)") (class "Default")
      (node (ref "C33") (pin "1") (pinfunction "1_1") (pintype "passive"))
      (node (ref "R27") (pin "2") (pinfunction "2_2") (pintype "passive"))
      (node (ref "U3") (pin "11") (pinfunction "REFIO_11") (pintype "bidirectional"))
    )
    (net (code "51") (name "Net-(U3-REGCAP)") (class "Default")
      (node (ref "C35") (pin "1") (pinfunction "1_1") (pintype "passive"))
      (node (ref "U3") (pin "3") (pinfunction "REGCAP_3") (pintype "bidirectional"))
    )
    (net (code "52") (name "Net-(U4A-+FB)") (class "Default")
      (node (ref "C39") (pin "2") (pinfunction "2_2") (pintype "passive"))
      (node (ref "R25") (pin "2") (pinfunction "2_2") (pintype "passive"))
      (node (ref "U4") (pin "2") (pinfunction "+FB_2") (pintype "output"))
    )
    (net (code "53") (name "Net-(U4A-+IN)") (class "Default")
      (node (ref "C32") (pin "1") (pinfunction "1_1") (pintype "passive"))
      (node (ref "R21") (pin "2") (pinfunction "2_2") (pintype "passive"))
      (node (ref "R22") (pin "1") (pinfunction "1_1") (pintype "passive"))
      (node (ref "U4") (pin "24") (pinfunction "+IN_24") (pintype "input"))
    )
    (net (code "54") (name "Net-(U4A-+OUT)") (class "Default")
      (node (ref "R26") (pin "1") (pinfunction "1_1") (pintype "passive"))
      (node (ref "U4") (pin "18") (pinfunction "+OUT_18") (pintype "output"))
    )
    (net (code "55") (name "Net-(U4A--FB)") (class "Default")
      (node (ref "C32") (pin "2") (pinfunction "2_2") (pintype "passive"))
      (node (ref "R22") (pin "2") (pinfunction "2_2") (pintype "passive"))
      (node (ref "U4") (pin "23") (pinfunction "-FB_23") (pintype "output"))
    )
    (net (code "56") (name "Net-(U4A--IN)") (class "Default")
      (node (ref "C39") (pin "1") (pinfunction "1_1") (pintype "passive"))
      (node (ref "R24") (pin "2") (pinfunction "2_2") (pintype "passive"))
      (node (ref "R25") (pin "1") (pinfunction "1_1") (pintype "passive"))
      (node (ref "U4") (pin "1") (pinfunction "-IN_1") (pintype "input"))
    )
    (net (code "57") (name "Net-(U4A--OUT)") (class "Default")
      (node (ref "R23") (pin "1") (pinfunction "1_1") (pintype "passive"))
      (node (ref "U4") (pin "19") (pinfunction "-OUT_19") (pintype "output"))
    )
    (net (code "58") (name "Net-(U4B-+FB)") (class "Default")
      (node (ref "C26") (pin "2") (pinfunction "2_2") (pintype "passive"))
      (node (ref "R19") (pin "2") (pinfunction "2_2") (pintype "passive"))
      (node (ref "U4") (pin "8") (pinfunction "+FB_8") (pintype "output"))
    )
    (net (code "59") (name "Net-(U4B-+IN)") (class "Default")
      (node (ref "C22") (pin "1") (pinfunction "1_1") (pintype "passive"))
      (node (ref "R15") (pin "2") (pinfunction "2_2") (pintype "passive"))
      (node (ref "R16") (pin "1") (pinfunction "1_1") (pintype "passive"))
      (node (ref "U4") (pin "6") (pinfunction "+IN_6") (pintype "input"))
    )
    (net (code "60") (name "Net-(U4B-+OUT)") (class "Default")
      (node (ref "R20") (pin "1") (pinfunction "1_1") (pintype "passive"))
      (node (ref "U4") (pin "12") (pinfunction "+OUT_12") (pintype "output"))
    )
    (net (code "61") (name "Net-(U4B--FB)") (class "Default")
      (node (ref "C22") (pin "2") (pinfunction "2_2") (pintype "passive"))
      (node (ref "R16") (pin "2") (pinfunction "2_2") (pintype "passive"))
      (node (ref "U4") (pin "5") (pinfunction "-FB_5") (pintype "output"))
    )
    (net (code "62") (name "Net-(U4B--IN)") (class "Default")
      (node (ref "C26") (pin "1") (pinfunction "1_1") (pintype "passive"))
      (node (ref "R18") (pin "2") (pinfunction "2_2") (pintype "passive"))
      (node (ref "R19") (pin "1") (pinfunction "1_1") (pintype "passive"))
      (node (ref "U4") (pin "7") (pinfunction "-IN_7") (pintype "input"))
    )
    (net (code "63") (name "Net-(U4B--OUT)") (class "Default")
      (node (ref "R17") (pin "1") (pinfunction "1_1") (pintype "passive"))
      (node (ref "U4") (pin "13") (pinfunction "-OUT_13") (pintype "output"))
    )
    (net (code "64") (name "Net-(U5-AINA+)") (class "Default")
      (node (ref "C45") (pin "2") (pinfunction "2_2") (pintype "passive"))
      (node (ref "C46") (pin "1") (pinfunction "1_1") (pintype "passive"))
      (node (ref "R34") (pin "2") (pinfunction "2_2") (pintype "passive"))
      (node (ref "U5") (pin "8") (pinfunction "AINA+_8") (pintype "input"))
    )
    (net (code "65") (name "Net-(U5-AINA-)") (class "Default")
      (node (ref "C44") (pin "2") (pinfunction "2_2") (pintype "passive"))
      (node (ref "C45") (pin "1") (pinfunction "1_1") (pintype "passive"))
      (node (ref "R31") (pin "2") (pinfunction "2_2") (pintype "passive"))
      (node (ref "U5") (pin "7") (pinfunction "AINA-_7") (pintype "input"))
    )
    (net (code "66") (name "Net-(U5-AINB+)") (class "Default")
      (node (ref "C58") (pin "2") (pinfunction "2_2") (pintype "passive"))
      (node (ref "C59") (pin "1") (pinfunction "1_1") (pintype "passive"))
      (node (ref "R40") (pin "2") (pinfunction "2_2") (pintype "passive"))
      (node (ref "U5") (pin "6") (pinfunction "AINB+_6") (pintype "input"))
    )
    (net (code "67") (name "Net-(U5-AINB-)") (class "Default")
      (node (ref "C57") (pin "2") (pinfunction "2_2") (pintype "passive"))
      (node (ref "C58") (pin "1") (pinfunction "1_1") (pintype "passive"))
      (node (ref "R37") (pin "2") (pinfunction "2_2") (pintype "passive"))
      (node (ref "U5") (pin "5") (pinfunction "AINB-_5") (pintype "input"))
    )
    (net (code "68") (name "Net-(U5-REFCAP)") (class "Default")
      (node (ref "C55") (pin "1") (pinfunction "1_1") (pintype "passive"))
      (node (ref "U5") (pin "9") (pinfunction "REFCAP_9") (pintype "bidirectional"))
    )
    (net (code "69") (name "Net-(U5-REFIO)") (class "Default")
      (node (ref "C54") (pin "1") (pinfunction "1_1") (pintype "passive"))
      (node (ref "R41") (pin "2") (pinfunction "2_2") (pintype "passive"))
      (node (ref "U5") (pin "11") (pinfunction "REFIO_11") (pintype "bidirectional"))
    )
    (net (code "70") (name "Net-(U5-REGCAP)") (class "Default")
      (node (ref "C56") (pin "1") (pinfunction "1_1") (pintype "passive"))
      (node (ref "U5") (pin "3") (pinfunction "REGCAP_3") (pintype "bidirectional"))
    )
    (net (code "71") (name "Net-(U6A-+FB)") (class "Default")
      (node (ref "C60") (pin "2") (pinfunction "2_2") (pintype "passive"))
      (node (ref "R39") (pin "2") (pinfunction "2_2") (pintype "passive"))
      (node (ref "U6") (pin "2") (pinfunction "+FB_2") (pintype "output"))
    )
    (net (code "72") (name "Net-(U6A-+IN)") (class "Default")
      (node (ref "C53") (pin "1") (pinfunction "1_1") (pintype "passive"))
      (node (ref "R35") (pin "2") (pinfunction "2_2") (pintype "passive"))
      (node (ref "R36") (pin "1") (pinfunction "1_1") (pintype "passive"))
      (node (ref "U6") (pin "24") (pinfunction "+IN_24") (pintype "input"))
    )
    (net (code "73") (name "Net-(U6A-+OUT)") (class "Default")
      (node (ref "R40") (pin "1") (pinfunction "1_1") (pintype "passive"))
      (node (ref "U6") (pin "18") (pinfunction "+OUT_18") (pintype "output"))
    )
    (net (code "74") (name "Net-(U6A--FB)") (class "Default")
      (node (ref "C53") (pin "2") (pinfunction "2_2") (pintype "passive"))
      (node (ref "R36") (pin "2") (pinfunction "2_2") (pintype "passive"))
      (node (ref "U6") (pin "23") (pinfunction "-FB_23") (pintype "output"))
    )
    (net (code "75") (name "Net-(U6A--IN)") (class "Default")
      (node (ref "C60") (pin "1") (pinfunction "1_1") (pintype "passive"))
      (node (ref "R38") (pin "2") (pinfunction "2_2") (pintype "passive"))
      (node (ref "R39") (pin "1") (pinfunction "1_1") (pintype "passive"))
      (node (ref "U6") (pin "1") (pinfunction "-IN_1") (pintype "input"))
    )
    (net (code "76") (name "Net-(U6A--OUT)") (class "Default")
      (node (ref "R37") (pin "1") (pinfunction "1_1") (pintype "passive"))
      (node (ref "U6") (pin "19") (pinfunction "-OUT_19") (pintype "output"))
    )
    (net (code "77") (name "Net-(U6B-+FB)") (class "Default")
      (node (ref "C47") (pin "2") (pinfunction "2_2") (pintype "passive"))
      (node (ref "R33") (pin "2") (pinfunction "2_2") (pintype "passive"))
      (node (ref "U6") (pin "8") (pinfunction "+FB_8") (pintype "output"))
    )
    (net (code "78") (name "Net-(U6B-+IN)") (class "Default")
      (node (ref "C43") (pin "1") (pinfunction "1_1") (pintype "passive"))
      (node (ref "R29") (pin "2") (pinfunction "2_2") (pintype "passive"))
      (node (ref "R30") (pin "1") (pinfunction "1_1") (pintype "passive"))
      (node (ref "U6") (pin "6") (pinfunction "+IN_6") (pintype "input"))
    )
    (net (code "79") (name "Net-(U6B-+OUT)") (class "Default")
      (node (ref "R34") (pin "1") (pinfunction "1_1") (pintype "passive"))
      (node (ref "U6") (pin "12") (pinfunction "+OUT_12") (pintype "output"))
    )
    (net (code "80") (name "Net-(U6B--FB)") (class "Default")
      (node (ref "C43") (pin "2") (pinfunction "2_2") (pintype "passive"))
      (node (ref "R30") (pin "2") (pinfunction "2_2") (pintype "passive"))
      (node (ref "U6") (pin "5") (pinfunction "-FB_5") (pintype "output"))
    )
    (net (code "81") (name "Net-(U6B--IN)") (class "Default")
      (node (ref "C47") (pin "1") (pinfunction "1_1") (pintype "passive"))
      (node (ref "R32") (pin "2") (pinfunction "2_2") (pintype "passive"))
      (node (ref "R33") (pin "1") (pinfunction "1_1") (pintype "passive"))
      (node (ref "U6") (pin "7") (pinfunction "-IN_7") (pintype "input"))
    )
    (net (code "82") (name "Net-(U6B--OUT)") (class "Default")
      (node (ref "R31") (pin "1") (pinfunction "1_1") (pintype "passive"))
      (node (ref "U6") (pin "13") (pinfunction "-OUT_13") (pintype "output"))
    )
    (net (code "83") (name "Net-(U7-AINA+)") (class "Default")
      (node (ref "C66") (pin "2") (pinfunction "2_2") (pintype "passive"))
      (node (ref "C67") (pin "1") (pinfunction "1_1") (pintype "passive"))
      (node (ref "R48") (pin "2") (pinfunction "2_2") (pintype "passive"))
      (node (ref "U7") (pin "8") (pinfunction "AINA+_8") (pintype "input"))
    )
    (net (code "84") (name "Net-(U7-AINA-)") (class "Default")
      (node (ref "C65") (pin "2") (pinfunction "2_2") (pintype "passive"))
      (node (ref "C66") (pin "1") (pinfunction "1_1") (pintype "passive"))
      (node (ref "R45") (pin "2") (pinfunction "2_2") (pintype "passive"))
      (node (ref "U7") (pin "7") (pinfunction "AINA-_7") (pintype "input"))
    )
    (net (code "85") (name "Net-(U7-AINB+)") (class "Default")
      (node (ref "C79") (pin "2") (pinfunction "2_2") (pintype "passive"))
      (node (ref "C80") (pin "1") (pinfunction "1_1") (pintype "passive"))
      (node (ref "R54") (pin "2") (pinfunction "2_2") (pintype "passive"))
      (node (ref "U7") (pin "6") (pinfunction "AINB+_6") (pintype "input"))
    )
    (net (code "86") (name "Net-(U7-AINB-)") (class "Default")
      (node (ref "C78") (pin "2") (pinfunction "2_2") (pintype "passive"))
      (node (ref "C79") (pin "1") (pinfunction "1_1") (pintype "passive"))
      (node (ref "R51") (pin "2") (pinfunction "2_2") (pintype "passive"))
      (node (ref "U7") (pin "5") (pinfunction "AINB-_5") (pintype "input"))
    )
    (net (code "87") (name "Net-(U7-REFCAP)") (class "Default")
      (node (ref "C76") (pin "1") (pinfunction "1_1") (pintype "passive"))
      (node (ref "U7") (pin "9") (pinfunction "REFCAP_9") (pintype "bidirectional"))
    )
    (net (code "88") (name "Net-(U7-REFIO)") (class "Default")
      (node (ref "C75") (pin "1") (pinfunction "1_1") (pintype "passive"))
      (node (ref "R55") (pin "2") (pinfunction "2_2") (pintype "passive"))
      (node (ref "U7") (pin "11") (pinfunction "REFIO_11") (pintype "bidirectional"))
    )
    (net (code "89") (name "Net-(U7-REGCAP)") (class "Default")
      (node (ref "C77") (pin "1") (pinfunction "1_1") (pintype "passive"))
      (node (ref "U7") (pin "3") (pinfunction "REGCAP_3") (pintype "bidirectional"))
    )
    (net (code "90") (name "Net-(U8A-+FB)") (class "Default")
      (node (ref "C81") (pin "2") (pinfunction "2_2") (pintype "passive"))
      (node (ref "R53") (pin "2") (pinfunction "2_2") (pintype "passive"))
      (node (ref "U8") (pin "2") (pinfunction "+FB_2") (pintype "output"))
    )
    (net (code "91") (name "Net-(U8A-+IN)") (class "Default")
      (node (ref "C74") (pin "1") (pinfunction "1_1") (pintype "passive"))
      (node (ref "R49") (pin "2") (pinfunction "2_2") (pintype "passive"))
      (node (ref "R50") (pin "1") (pinfunction "1_1") (pintype "passive"))
      (node (ref "U8") (pin "24") (pinfunction "+IN_24") (pintype "input"))
    )
    (net (code "92") (name "Net-(U8A-+OUT)") (class "Default")
      (node (ref "R54") (pin "1") (pinfunction "1_1") (pintype "passive"))
      (node (ref "U8") (pin "18") (pinfunction "+OUT_18") (pintype "output"))
    )
    (net (code "93") (name "Net-(U8A--FB)") (class "Default")
      (node (ref "C74") (pin "2") (pinfunction "2_2") (pintype "passive"))
      (node (ref "R50") (pin "2") (pinfunction "2_2") (pintype "passive"))
      (node (ref "U8") (pin "23") (pinfunction "-FB_23") (pintype "output"))
    )
    (net (code "94") (name "Net-(U8A--IN)") (class "Default")
      (node (ref "C81") (pin "1") (pinfunction "1_1") (pintype "passive"))
      (node (ref "R52") (pin "2") (pinfunction "2_2") (pintype "passive"))
      (node (ref "R53") (pin "1") (pinfunction "1_1") (pintype "passive"))
      (node (ref "U8") (pin "1") (pinfunction "-IN_1") (pintype "input"))
    )
    (net (code "95") (name "Net-(U8A--OUT)") (class "Default")
      (node (ref "R51") (pin "1") (pinfunction "1_1") (pintype "passive"))
      (node (ref "U8") (pin "19") (pinfunction "-OUT_19") (pintype "output"))
    )
    (net (code "96") (name "Net-(U8B-+FB)") (class "Default")
      (node (ref "C68") (pin "2") (pinfunction "2_2") (pintype "passive"))
      (node (ref "R47") (pin "2") (pinfunction "2_2") (pintype "passive"))
      (node (ref "U8") (pin "8") (pinfunction "+FB_8") (pintype "output"))
    )
    (net (code "97") (name "Net-(U8B-+IN)") (class "Default")
      (node (ref "C64") (pin "1") (pinfunction "1_1") (pintype "passive"))
      (node (ref "R43") (pin "2") (pinfunction "2_2") (pintype "passive"))
      (node (ref "R44") (pin "1") (pinfunction "1_1") (pintype "passive"))
      (node (ref "U8") (pin "6") (pinfunction "+IN_6") (pintype "input"))
    )
    (net (code "98") (name "Net-(U8B-+OUT)") (class "Default")
      (node (ref "R48") (pin "1") (pinfunction "1_1") (pintype "passive"))
      (node (ref "U8") (pin "12") (pinfunction "+OUT_12") (pintype "output"))
    )
    (net (code "99") (name "Net-(U8B--FB)") (class "Default")
      (node (ref "C64") (pin "2") (pinfunction "2_2") (pintype "passive"))
      (node (ref "R44") (pin "2") (pinfunction "2_2") (pintype "passive"))
      (node (ref "U8") (pin "5") (pinfunction "-FB_5") (pintype "output"))
    )
    (net (code "100") (name "Net-(U8B--IN)") (class "Default")
      (node (ref "C68") (pin "1") (pinfunction "1_1") (pintype "passive"))
      (node (ref "R46") (pin "2") (pinfunction "2_2") (pintype "passive"))
      (node (ref "R47") (pin "1") (pinfunction "1_1") (pintype "passive"))
      (node (ref "U8") (pin "7") (pinfunction "-IN_7") (pintype "input"))
    )
    (net (code "101") (name "Net-(U8B--OUT)") (class "Default")
      (node (ref "R45") (pin "1") (pinfunction "1_1") (pintype "passive"))
      (node (ref "U8") (pin "13") (pinfunction "-OUT_13") (pintype "output"))
    )
    (net (code "102") (name "Net-(U10B-USB_DN)") (class "Default")
      (node (ref "R61") (pin "1") (pinfunction "1_1") (pintype "passive"))
      (node (ref "U10") (pin "46") (pinfunction "USB_DN_46") (pintype "bidirectional"))
    )
    (net (code "103") (name "Net-(U10B-USB_DP)") (class "Default")
      (node (ref "R60") (pin "1") (pinfunction "1_1") (pintype "passive"))
      (node (ref "U10") (pin "47") (pinfunction "USB_DP_47") (pintype "bidirectional"))
    )
    (net (code "104") (name "Net-(U10B-XIN)") (class "Default")
      (node (ref "C87") (pin "1") (pinfunction "1_1") (pintype "passive"))
      (node (ref "U10") (pin "20") (pinfunction "XIN_20") (pintype "bidirectional"))
      (node (ref "X1") (pin "3") (pinfunction "C2_3") (pintype "passive"))
    )
    (net (code "105") (name "Net-(U10B-XOUT)") (class "Default")
      (node (ref "R64") (pin "1") (pinfunction "1_1") (pintype "passive"))
      (node (ref "U10") (pin "21") (pinfunction "XOUT_21") (pintype "bidirectional"))
    )
    (net (code "106") (name "Net-(U10C-ADC_VDD)") (class "Default")
      (node (ref "C93") (pin "1") (pinfunction "1_1") (pintype "passive"))
      (node (ref "R65") (pin "2") (pinfunction "2_2") (pintype "passive"))
      (node (ref "U10") (pin "43") (pinfunction "ADC_VDD_43") (pintype "power_in"))
    )
    (net (code "107") (name "Net-(U13-SENSE{slash}ADJ)") (class "Default")
      (node (ref "R66") (pin "1") (pinfunction "1_1") (pintype "passive"))
      (node (ref "R67") (pin "2") (pinfunction "2_2") (pintype "passive"))
      (node (ref "U13") (pin "2") (pinfunction "SENSE/ADJ_2") (pintype "input"))
    )
    (net (code "108") (name "Net-(U15-NC{slash}ADJ)") (class "Default")
      (node (ref "R68") (pin "1") (pinfunction "1_1") (pintype "passive"))
      (node (ref "R69") (pin "2") (pinfunction "2_2") (pintype "passive"))
      (node (ref "R70") (pin "2") (pinfunction "2_2") (pintype "passive"))
      (node (ref "U15") (pin "2") (pinfunction "NC/ADJ_2") (pintype "bidirectional"))
    )
    (net (code "109") (name "Net-(X1-C1)") (class "Default")
      (node (ref "C86") (pin "1") (pinfunction "1_1") (pintype "passive"))
      (node (ref "R64") (pin "2") (pinfunction "2_2") (pintype "passive"))
      (node (ref "X1") (pin "1") (pinfunction "C1_1") (pintype "passive"))
    )
    (net (code "110") (name "OPT_EN_VN") (class "Default")
      (node (ref "U10") (pin "12") (pinfunction "GPIO09_12") (pintype "bidirectional"))
      (node (ref "U15") (pin "3") (pinfunction "EN_3") (pintype "bidirectional"))
    )
    (net (code "111") (name "OPT_EN_VP") (class "Default")
      (node (ref "U10") (pin "11") (pinfunction "GPIO08_11") (pintype "bidirectional"))
      (node (ref "U13") (pin "4") (pinfunction "EN_4") (pintype "input"))
    )
    (net (code "112") (name "QSPI_SCLK") (class "Default")
      (node (ref "U10") (pin "52") (pinfunction "QSPI_SCLK_52") (pintype "output"))
      (node (ref "U9") (pin "6") (pinfunction "CLK_6") (pintype "input"))
    )
    (net (code "113") (name "QSPI_SD0") (class "Default")
      (node (ref "U10") (pin "53") (pinfunction "QSPI_SD0_53") (pintype "bidirectional"))
      (node (ref "U9") (pin "5") (pinfunction "DI/IO[0]_5") (pintype "bidirectional"))
    )
    (net (code "114") (name "QSPI_SD1") (class "Default")
      (node (ref "U10") (pin "55") (pinfunction "QSPI_SD1_55") (pintype "bidirectional"))
      (node (ref "U9") (pin "2") (pinfunction "DO/IO[1]_2") (pintype "bidirectional"))
    )
    (net (code "115") (name "QSPI_SD2") (class "Default")
      (node (ref "U10") (pin "54") (pinfunction "QSPI_SD2_54") (pintype "bidirectional"))
      (node (ref "U9") (pin "3") (pinfunction "#WP/IO[2]_3") (pintype "bidirectional"))
    )
    (net (code "116") (name "QSPI_SD3") (class "Default")
      (node (ref "U10") (pin "51") (pinfunction "QSPI_SD3_51") (pintype "bidirectional"))
      (node (ref "U9") (pin "7") (pinfunction "#HOLD/IO[3]_7") (pintype "bidirectional"))
    )
    (net (code "117") (name "QSPI_SS_N") (class "Default")
      (node (ref "R57") (pin "2") (pinfunction "2_2") (pintype "passive"))
      (node (ref "R58") (pin "1") (pinfunction "1_1") (pintype "passive"))
      (node (ref "U10") (pin "56") (pinfunction "QSPI_SS_N_56") (pintype "output"))
      (node (ref "U9") (pin "1") (pinfunction "/CS_1") (pintype "input"))
    )
    (net (code "118") (name "RUN") (class "Default")
      (node (ref "J5") (pin "B7") (pinfunction "13_B7") (pintype "passive"))
      (node (ref "R59") (pin "1") (pinfunction "1_1") (pintype "passive"))
      (node (ref "U10") (pin "26") (pinfunction "RUN_26") (pintype "input"))
    )
    (net (code "119") (name "SCLK_A1") (class "Default")
      (node (ref "U1") (pin "16") (pinfunction "SCLK_16") (pintype "input"))
      (node (ref "U10") (pin "28") (pinfunction "GPIO17_28") (pintype "bidirectional"))
    )
    (net (code "120") (name "SCLK_A2") (class "Default")
      (node (ref "U10") (pin "38") (pinfunction "GPIO26/ADC0_38") (pintype "bidirectional"))
      (node (ref "U3") (pin "16") (pinfunction "SCLK_16") (pintype "input"))
    )
    (net (code "121") (name "SCLK_A3") (class "Default")
      (node (ref "J2") (pin "10") (pinfunction "10_10") (pintype "passive"))
      (node (ref "U10") (pin "16") (pinfunction "GPIO13_16") (pintype "bidirectional"))
      (node (ref "U5") (pin "16") (pinfunction "SCLK_16") (pintype "input"))
    )
    (net (code "122") (name "SCLK_A4") (class "Default")
      (node (ref "U10") (pin "34") (pinfunction "GPIO22_34") (pintype "bidirectional"))
      (node (ref "U7") (pin "16") (pinfunction "SCLK_16") (pintype "input"))
    )
    (net (code "123") (name "SDI_A1") (class "Default")
      (node (ref "U1") (pin "15") (pinfunction "SDI_15") (pintype "input"))
      (node (ref "U10") (pin "29") (pinfunction "GPIO18_29") (pintype "bidirectional"))
    )
    (net (code "124") (name "SDI_A2") (class "Default")
      (node (ref "U10") (pin "39") (pinfunction "GPIO27/ADC1_39") (pintype "bidirectional"))
      (node (ref "U3") (pin "15") (pinfunction "SDI_15") (pintype "input"))
    )
    (net (code "125") (name "SDI_A3") (class "Default")
      (node (ref "J2") (pin "8") (pinfunction "8_8") (pintype "passive"))
      (node (ref "U10") (pin "17") (pinfunction "GPIO14_17") (pintype "bidirectional"))
      (node (ref "U5") (pin "15") (pinfunction "SDI_15") (pintype "input"))
    )
    (net (code "126") (name "SDI_A4") (class "Default")
      (node (ref "U10") (pin "35") (pinfunction "GPIO23_35") (pintype "bidirectional"))
      (node (ref "U7") (pin "15") (pinfunction "SDI_15") (pintype "input"))
    )
    (net (code "127") (name "SDOA_A1") (class "Default")
      (node (ref "U1") (pin "13") (pinfunction "SDOA_13") (pintype "output"))
      (node (ref "U10") (pin "31") (pinfunction "GPIO20_31") (pintype "bidirectional"))
    )
    (net (code "128") (name "SDOA_A2") (class "Default")
      (node (ref "U10") (pin "41") (pinfunction "GPIO29/ADC3_41") (pintype "bidirectional"))
      (node (ref "U3") (pin "13") (pinfunction "SDOA_13") (pintype "output"))
    )
    (net (code "129") (name "SDOA_A3") (class "Default")
      (node (ref "J2") (pin "4") (pinfunction "4_4") (pintype "passive"))
      (node (ref "U10") (pin "18") (pinfunction "GPIO15_18") (pintype "bidirectional"))
      (node (ref "U5") (pin "13") (pinfunction "SDOA_13") (pintype "output"))
    )
    (net (code "130") (name "SDOA_A4") (class "Default")
      (node (ref "U10") (pin "36") (pinfunction "GPIO24_36") (pintype "bidirectional"))
      (node (ref "U7") (pin "13") (pinfunction "SDOA_13") (pintype "output"))
    )
    (net (code "131") (name "SDOB_A1") (class "Default")
      (node (ref "U1") (pin "14") (pinfunction "SDOB_14") (pintype "output"))
      (node (ref "U10") (pin "30") (pinfunction "GPIO19_30") (pintype "bidirectional"))
    )
    (net (code "132") (name "SDOB_A2") (class "Default")
      (node (ref "U10") (pin "40") (pinfunction "GPIO28/ADC2_40") (pintype "bidirectional"))
      (node (ref "U3") (pin "14") (pinfunction "SDOB_14") (pintype "output"))
    )
    (net (code "133") (name "SDOB_A3") (class "Default")
      (node (ref "J2") (pin "6") (pinfunction "6_6") (pintype "passive"))
      (node (ref "U10") (pin "14") (pinfunction "GPIO11_14") (pintype "bidirectional"))
      (node (ref "U5") (pin "14") (pinfunction "SDOB_14") (pintype "output"))
    )
    (net (code "134") (name "SDOB_A4") (class "Default")
      (node (ref "U10") (pin "13") (pinfunction "GPIO10_13") (pintype "bidirectional"))
      (node (ref "U7") (pin "14") (pinfunction "SDOB_14") (pintype "output"))
    )
    (net (code "135") (name "SWCLK") (class "Default")
      (node (ref "J3") (pin "1") (pinfunction "1_1") (pintype "passive"))
      (node (ref "J5") (pin "B6") (pinfunction "11_B6") (pintype "passive"))
      (node (ref "U10") (pin "24") (pinfunction "SWCLK_24") (pintype "input"))
    )
    (net (code "136") (name "SWDIO") (class "Default")
      (node (ref "J3") (pin "3") (pinfunction "3_3") (pintype "passive"))
      (node (ref "J5") (pin "B5") (pinfunction "9_B5") (pintype "passive"))
      (node (ref "U10") (pin "25") (pinfunction "SWDIO_25") (pintype "bidirectional"))
    )
    (net (code "137") (name "V1P1") (class "Default")
      (node (ref "C91") (pin "1") (pinfunction "1_1") (pintype "passive"))
      (node (ref "C96") (pin "1") (pinfunction "1_1") (pintype "passive"))
      (node (ref "C97") (pin "1") (pinfunction "1_1") (pintype "passive"))
      (node (ref "TP21") (pin "P$1") (pinfunction "P$1_P$1") (pintype "bidirectional"))
      (node (ref "U10") (pin "23") (pinfunction "DVDD_23") (pintype "power_in"))
      (node (ref "U10") (pin "45") (pinfunction "VREG_VOUT_45") (pintype "power_in"))
      (node (ref "U10") (pin "50") (pinfunction "DVDD_50") (pintype "power_in"))
    )
    (net (code "138") (name "V3P3") (class "Default")
      (node (ref "C100") (pin "1") (pinfunction "1_1") (pintype "passive"))
      (node (ref "C101") (pin "1") (pinfunction "1_1") (pintype "passive"))
      (node (ref "C102") (pin "1") (pinfunction "1_1") (pintype "passive"))
      (node (ref "C103") (pin "1") (pinfunction "1_1") (pintype "passive"))
      (node (ref "C113") (pin "1") (pinfunction "1_1") (pintype "passive"))
      (node (ref "C28") (pin "1") (pinfunction "1_1") (pintype "passive"))
      (node (ref "C49") (pin "1") (pinfunction "1_1") (pintype "passive"))
      (node (ref "C7") (pin "1") (pinfunction "1_1") (pintype "passive"))
      (node (ref "C70") (pin "1") (pinfunction "1_1") (pintype "passive"))
      (node (ref "C85") (pin "1") (pinfunction "1_1") (pintype "passive"))
      (node (ref "C90") (pin "1") (pinfunction "1_1") (pintype "passive"))
      (node (ref "C92") (pin "1") (pinfunction "1_1") (pintype "passive"))
      (node (ref "C98") (pin "1") (pinfunction "1_1") (pintype "passive"))
      (node (ref "C99") (pin "1") (pinfunction "1_1") (pintype "passive"))
      (node (ref "J5") (pin "B16") (pinfunction "31_B16") (pintype "passive"))
      (node (ref "R58") (pin "2") (pinfunction "2_2") (pintype "passive"))
      (node (ref "R59") (pin "2") (pinfunction "2_2") (pintype "passive"))
      (node (ref "R65") (pin "1") (pinfunction "1_1") (pintype "passive"))
      (node (ref "TP17") (pin "P$1") (pinfunction "P$1_P$1") (pintype "bidirectional"))
      (node (ref "U1") (pin "2") (pinfunction "VLOGIC_2") (pintype "power_in"))
      (node (ref "U10") (pin "1") (pinfunction "IOVDD_1") (pintype "power_in"))
      (node (ref "U10") (pin "10") (pinfunction "IOVDD_10") (pintype "power_in"))
      (node (ref "U10") (pin "22") (pinfunction "IOVDD_22") (pintype "power_in"))
      (node (ref "U10") (pin "33") (pinfunction "IOVDD_33") (pintype "power_in"))
      (node (ref "U10") (pin "42") (pinfunction "IOVDD_42") (pintype "power_in"))
      (node (ref "U10") (pin "44") (pinfunction "VREG_VIN_44") (pintype "power_in"))
      (node (ref "U10") (pin "48") (pinfunction "USB_VDD_48") (pintype "power_in"))
      (node (ref "U10") (pin "49") (pinfunction "IOVDD_49") (pintype "power_in"))
      (node (ref "U11") (pin "1") (pinfunction "OUT_1") (pintype "power_in"))
      (node (ref "U3") (pin "2") (pinfunction "VLOGIC_2") (pintype "power_in"))
      (node (ref "U5") (pin "2") (pinfunction "VLOGIC_2") (pintype "power_in"))
      (node (ref "U7") (pin "2") (pinfunction "VLOGIC_2") (pintype "power_in"))
      (node (ref "U9") (pin "8") (pinfunction "VCC_8") (pintype "power_in"))
    )
    (net (code "139") (name "V3P3A") (class "Default")
      (node (ref "C111") (pin "1") (pinfunction "1_1") (pintype "passive"))
      (node (ref "C19") (pin "1") (pinfunction "1_1") (pintype "passive"))
      (node (ref "C27") (pin "1") (pinfunction "1_1") (pintype "passive"))
      (node (ref "C29") (pin "1") (pinfunction "1_1") (pintype "passive"))
      (node (ref "C40") (pin "1") (pinfunction "1_1") (pintype "passive"))
      (node (ref "C48") (pin "1") (pinfunction "1_1") (pintype "passive"))
      (node (ref "C50") (pin "1") (pinfunction "1_1") (pintype "passive"))
      (node (ref "C6") (pin "1") (pinfunction "1_1") (pintype "passive"))
      (node (ref "C61") (pin "1") (pinfunction "1_1") (pintype "passive"))
      (node (ref "C69") (pin "1") (pinfunction "1_1") (pintype "passive"))
      (node (ref "C71") (pin "1") (pinfunction "1_1") (pintype "passive"))
      (node (ref "C8") (pin "1") (pinfunction "1_1") (pintype "passive"))
      (node (ref "C82") (pin "1") (pinfunction "1_1") (pintype "passive"))
      (node (ref "C95") (pin "1") (pinfunction "1_1") (pintype "passive"))
      (node (ref "TP18") (pin "P$1") (pinfunction "P$1_P$1") (pintype "bidirectional"))
      (node (ref "U1") (pin "4") (pinfunction "VCC_4") (pintype "power_in"))
      (node (ref "U12") (pin "1") (pinfunction "OUT_1") (pintype "power_in"))
      (node (ref "U2") (pin "10") (pinfunction "+VS_10") (pintype "power_in"))
      (node (ref "U2") (pin "3") (pinfunction "+VS_3") (pintype "power_in"))
      (node (ref "U2") (pin "4") (pinfunction "+VS_4") (pintype "power_in"))
      (node (ref "U2") (pin "9") (pinfunction "+VS_9") (pintype "power_in"))
      (node (ref "U3") (pin "4") (pinfunction "VCC_4") (pintype "power_in"))
      (node (ref "U4") (pin "10") (pinfunction "+VS_10") (pintype "power_in"))
      (node (ref "U4") (pin "3") (pinfunction "+VS_3") (pintype "power_in"))
      (node (ref "U4") (pin "4") (pinfunction "+VS_4") (pintype "power_in"))
      (node (ref "U4") (pin "9") (pinfunction "+VS_9") (pintype "power_in"))
      (node (ref "U5") (pin "4") (pinfunction "VCC_4") (pintype "power_in"))
      (node (ref "U6") (pin "10") (pinfunction "+VS_10") (pintype "power_in"))
      (node (ref "U6") (pin "3") (pinfunction "+VS_3") (pintype "power_in"))
      (node (ref "U6") (pin "4") (pinfunction "+VS_4") (pintype "power_in"))
      (node (ref "U6") (pin "9") (pinfunction "+VS_9") (pintype "power_in"))
      (node (ref "U7") (pin "4") (pinfunction "VCC_4") (pintype "power_in"))
      (node (ref "U8") (pin "10") (pinfunction "+VS_10") (pintype "power_in"))
      (node (ref "U8") (pin "3") (pinfunction "+VS_3") (pintype "power_in"))
      (node (ref "U8") (pin "4") (pinfunction "+VS_4") (pintype "power_in"))
      (node (ref "U8") (pin "9") (pinfunction "+VS_9") (pintype "power_in"))
    )
    (net (code "140") (name "V5P0") (class "Default")
      (node (ref "C88") (pin "1") (pinfunction "1_1") (pintype "passive"))
      (node (ref "C89") (pin "1") (pinfunction "1_1") (pintype "passive"))
      (node (ref "C94") (pin "1") (pinfunction "1_1") (pintype "passive"))
      (node (ref "D1") (pin "C") (pinfunction "C_C") (pintype "bidirectional"))
      (node (ref "D2") (pin "C") (pinfunction "C_C") (pintype "bidirectional"))
      (node (ref "TP22") (pin "P$1") (pinfunction "P$1_P$1") (pintype "bidirectional"))
      (node (ref "U11") (pin "5") (pinfunction "/SHDN_5") (pintype "input"))
      (node (ref "U11") (pin "8") (pinfunction "IN_8") (pintype "power_in"))
      (node (ref "U12") (pin "5") (pinfunction "/SHDN_5") (pintype "input"))
      (node (ref "U12") (pin "8") (pinfunction "IN_8") (pintype "power_in"))
    )
    (net (code "141") (name "V5P0_IN") (class "Default")
      (node (ref "D1") (pin "A") (pinfunction "A_A") (pintype "bidirectional"))
      (node (ref "J5") (pin "A1") (pinfunction "2_A1") (pintype "passive"))
      (node (ref "J5") (pin "A3") (pinfunction "6_A3") (pintype "passive"))
      (node (ref "J5") (pin "B1") (pinfunction "1_B1") (pintype "passive"))
      (node (ref "J5") (pin "B3") (pinfunction "5_B3") (pintype "passive"))
    )
    (net (code "142") (name "V6P5") (class "Default")
      (node (ref "C105") (pin "1") (pinfunction "1_1") (pintype "passive"))
      (node (ref "LF1") (pin "2") (pinfunction "P$2_2") (pintype "bidirectional"))
      (node (ref "R66") (pin "2") (pinfunction "2_2") (pintype "passive"))
      (node (ref "U13") (pin "1") (pinfunction "VOUT_1") (pintype "power_in"))
    )
    (net (code "143") (name "V9P0") (class "Default")
      (node (ref "C104") (pin "1") (pinfunction "1_1") (pintype "passive"))
      (node (ref "J5") (pin "A18") (pinfunction "36_A18") (pintype "passive"))
      (node (ref "R71") (pin "2") (pinfunction "2_2") (pintype "passive"))
      (node (ref "U13") (pin "6") (pinfunction "VIN_6") (pintype "power_in"))
    )
    (net (code "144") (name "VBUS") (class "Default")
      (node (ref "D2") (pin "A") (pinfunction "A_A") (pintype "bidirectional"))
      (node (ref "J4") (pin "1") (pinfunction "1_1") (pintype "bidirectional"))
    )
    (net (code "145") (name "VN1P2") (class "Default")
      (node (ref "C10") (pin "1") (pinfunction "1_1") (pintype "passive"))
      (node (ref "C107") (pin "2") (pinfunction "2_2") (pintype "passive"))
      (node (ref "C112") (pin "2") (pinfunction "2_2") (pintype "passive"))
      (node (ref "C21") (pin "1") (pinfunction "1_1") (pintype "passive"))
      (node (ref "C31") (pin "1") (pinfunction "1_1") (pintype "passive"))
      (node (ref "C42") (pin "1") (pinfunction "1_1") (pintype "passive"))
      (node (ref "C52") (pin "1") (pinfunction "1_1") (pintype "passive"))
      (node (ref "C63") (pin "1") (pinfunction "1_1") (pintype "passive"))
      (node (ref "C73") (pin "1") (pinfunction "1_1") (pintype "passive"))
      (node (ref "C84") (pin "1") (pinfunction "1_1") (pintype "passive"))
      (node (ref "TP19") (pin "P$1") (pinfunction "P$1_P$1") (pintype "bidirectional"))
      (node (ref "U14") (pin "1") (pinfunction "OUT_1") (pintype "bidirectional"))
      (node (ref "U14") (pin "2") (pinfunction "NC/ADJ_2") (pintype "bidirectional"))
      (node (ref "U2") (pin "15") (pinfunction "-VS_15") (pintype "power_in"))
      (node (ref "U2") (pin "16") (pinfunction "-VS_16") (pintype "power_in"))
      (node (ref "U2") (pin "21") (pinfunction "-VS_21") (pintype "power_in"))
      (node (ref "U2") (pin "22") (pinfunction "-VS_22") (pintype "power_in"))
      (node (ref "U4") (pin "15") (pinfunction "-VS_15") (pintype "power_in"))
      (node (ref "U4") (pin "16") (pinfunction "-VS_16") (pintype "power_in"))
      (node (ref "U4") (pin "21") (pinfunction "-VS_21") (pintype "power_in"))
      (node (ref "U4") (pin "22") (pinfunction "-VS_22") (pintype "power_in"))
      (node (ref "U6") (pin "15") (pinfunction "-VS_15") (pintype "power_in"))
      (node (ref "U6") (pin "16") (pinfunction "-VS_16") (pintype "power_in"))
      (node (ref "U6") (pin "21") (pinfunction "-VS_21") (pintype "power_in"))
      (node (ref "U6") (pin "22") (pinfunction "-VS_22") (pintype "power_in"))
      (node (ref "U8") (pin "15") (pinfunction "-VS_15") (pintype "power_in"))
      (node (ref "U8") (pin "16") (pinfunction "-VS_16") (pintype "power_in"))
      (node (ref "U8") (pin "21") (pinfunction "-VS_21") (pintype "power_in"))
      (node (ref "U8") (pin "22") (pinfunction "-VS_22") (pintype "power_in"))
    )
    (net (code "146") (name "VN3P0") (class "Default")
      (node (ref "C106") (pin "2") (pinfunction "2_2") (pintype "passive"))
      (node (ref "J5") (pin "A19") (pinfunction "38_A19") (pintype "passive"))
      (node (ref "U14") (pin "3") (pinfunction "EN_3") (pintype "bidirectional"))
      (node (ref "U14") (pin "6") (pinfunction "IN_6") (pintype "bidirectional"))
      (node (ref "U14") (pin "PAD") (pinfunction "IN_PAD") (pintype "bidirectional"))
    )
    (net (code "147") (name "VN20P0") (class "Default")
      (node (ref "C109") (pin "2") (pinfunction "2_2") (pintype "passive"))
      (node (ref "C110") (pin "2") (pinfunction "2_2") (pintype "passive"))
      (node (ref "LF2") (pin "2") (pinfunction "P$2_2") (pintype "bidirectional"))
      (node (ref "R69") (pin "1") (pinfunction "1_1") (pintype "passive"))
      (node (ref "U15") (pin "1") (pinfunction "OUT_1") (pintype "bidirectional"))
    )
    (net (code "148") (name "VN22") (class "Default")
      (node (ref "C108") (pin "2") (pinfunction "2_2") (pintype "passive"))
      (node (ref "J5") (pin "B20") (pinfunction "39_B20") (pintype "passive"))
      (node (ref "U15") (pin "6") (pinfunction "IN_6") (pintype "bidirectional"))
      (node (ref "U15") (pin "PAD") (pinfunction "IN_PAD") (pintype "bidirectional"))
    )
    (net (code "149") (name "VOCM_A1") (class "Default")
      (node (ref "C20") (pin "1") (pinfunction "1_1") (pintype "passive"))
      (node (ref "C9") (pin "1") (pinfunction "1_1") (pintype "passive"))
      (node (ref "R13") (pin "1") (pinfunction "1_1") (pintype "passive"))
      (node (ref "R14") (pin "2") (pinfunction "2_2") (pintype "passive"))
      (node (ref "TP5") (pin "P$1") (pinfunction "P$1_P$1") (pintype "bidirectional"))
      (node (ref "U2") (pin "11") (pinfunction "VOCM_11") (pintype "input"))
      (node (ref "U2") (pin "17") (pinfunction "VOCM_17") (pintype "input"))
    )
    (net (code "150") (name "VOCM_A2") (class "Default")
      (node (ref "C30") (pin "1") (pinfunction "1_1") (pintype "passive"))
      (node (ref "C41") (pin "1") (pinfunction "1_1") (pintype "passive"))
      (node (ref "R27") (pin "1") (pinfunction "1_1") (pintype "passive"))
      (node (ref "R28") (pin "2") (pinfunction "2_2") (pintype "passive"))
      (node (ref "TP8") (pin "P$1") (pinfunction "P$1_P$1") (pintype "bidirectional"))
      (node (ref "U4") (pin "11") (pinfunction "VOCM_11") (pintype "input"))
      (node (ref "U4") (pin "17") (pinfunction "VOCM_17") (pintype "input"))
    )
    (net (code "151") (name "VOCM_A3") (class "Default")
      (node (ref "C51") (pin "1") (pinfunction "1_1") (pintype "passive"))
      (node (ref "C62") (pin "1") (pinfunction "1_1") (pintype "passive"))
      (node (ref "R41") (pin "1") (pinfunction "1_1") (pintype "passive"))
      (node (ref "R42") (pin "2") (pinfunction "2_2") (pintype "passive"))
      (node (ref "TP12") (pin "P$1") (pinfunction "P$1_P$1") (pintype "bidirectional"))
      (node (ref "U6") (pin "11") (pinfunction "VOCM_11") (pintype "input"))
      (node (ref "U6") (pin "17") (pinfunction "VOCM_17") (pintype "input"))
    )
    (net (code "152") (name "VOCM_A4") (class "Default")
      (node (ref "C72") (pin "1") (pinfunction "1_1") (pintype "passive"))
      (node (ref "C83") (pin "1") (pinfunction "1_1") (pintype "passive"))
      (node (ref "R55") (pin "1") (pinfunction "1_1") (pintype "passive"))
      (node (ref "R56") (pin "2") (pinfunction "2_2") (pintype "passive"))
      (node (ref "TP16") (pin "P$1") (pinfunction "P$1_P$1") (pintype "bidirectional"))
      (node (ref "U8") (pin "11") (pinfunction "VOCM_11") (pintype "input"))
      (node (ref "U8") (pin "17") (pinfunction "VOCM_17") (pintype "input"))
    )
    (net (code "153") (name "unconnected-(J1-Pad34)") (class "Default")
      (node (ref "J1") (pin "34") (pinfunction "34_34") (pintype "passive"))
    )
    (net (code "154") (name "unconnected-(J4-Pad4)") (class "Default")
      (node (ref "J4") (pin "4") (pinfunction "4_4") (pintype "bidirectional"))
    )
    (net (code "155") (name "unconnected-(U2A-{slash}DISABLE-Pad20)") (class "Default")
      (node (ref "U2") (pin "20") (pinfunction "/DISABLE_20") (pintype "input"))
    )
    (net (code "156") (name "unconnected-(U2B-{slash}DISABLE-Pad14)") (class "Default")
      (node (ref "U2") (pin "14") (pinfunction "/DISABLE_14") (pintype "input"))
    )
    (net (code "157") (name "unconnected-(U4A-{slash}DISABLE-Pad20)") (class "Default")
      (node (ref "U4") (pin "20") (pinfunction "/DISABLE_20") (pintype "input"))
    )
    (net (code "158") (name "unconnected-(U4B-{slash}DISABLE-Pad14)") (class "Default")
      (node (ref "U4") (pin "14") (pinfunction "/DISABLE_14") (pintype "input"))
    )
    (net (code "159") (name "unconnected-(U6A-{slash}DISABLE-Pad20)") (class "Default")
      (node (ref "U6") (pin "20") (pinfunction "/DISABLE_20") (pintype "input"))
    )
    (net (code "160") (name "unconnected-(U6B-{slash}DISABLE-Pad14)") (class "Default")
      (node (ref "U6") (pin "14") (pinfunction "/DISABLE_14") (pintype "input"))
    )
    (net (code "161") (name "unconnected-(U8A-{slash}DISABLE-Pad20)") (class "Default")
      (node (ref "U8") (pin "20") (pinfunction "/DISABLE_20") (pintype "input"))
    )
    (net (code "162") (name "unconnected-(U8B-{slash}DISABLE-Pad14)") (class "Default")
      (node (ref "U8") (pin "14") (pinfunction "/DISABLE_14") (pintype "input"))
    )
    (net (code "163") (name "unconnected-(U11-PWRGD-Pad2)") (class "Default")
      (node (ref "U11") (pin "2") (pinfunction "PWRGD_2") (pintype "output"))
    )
    (net (code "164") (name "unconnected-(U12-PWRGD-Pad2)") (class "Default")
      (node (ref "U12") (pin "2") (pinfunction "PWRGD_2") (pintype "output"))
    )
    (net (code "165") (name "unconnected-(U13-SS-Pad5)") (class "Default")
      (node (ref "U13") (pin "5") (pinfunction "SS_5") (pintype "bidirectional"))
    )
    (net (code "166") (name "{slash}CS_A1") (class "Default")
      (node (ref "U1") (pin "12") (pinfunction "/CS_12") (pintype "input"))
      (node (ref "U10") (pin "27") (pinfunction "GPIO16_27") (pintype "bidirectional"))
    )
    (net (code "167") (name "{slash}CS_A2") (class "Default")
      (node (ref "U10") (pin "37") (pinfunction "GPIO25_37") (pintype "bidirectional"))
      (node (ref "U3") (pin "12") (pinfunction "/CS_12") (pintype "input"))
    )
    (net (code "168") (name "{slash}CS_A3") (class "Default")
      (node (ref "J2") (pin "2") (pinfunction "2_2") (pintype "passive"))
      (node (ref "U10") (pin "15") (pinfunction "GPIO12_15") (pintype "bidirectional"))
      (node (ref "U5") (pin "12") (pinfunction "/CS_12") (pintype "input"))
    )
    (net (code "169") (name "{slash}CS_A4") (class "Default")
      (node (ref "U10") (pin "32") (pinfunction "GPIO21_32") (pintype "bidirectional"))
      (node (ref "U7") (pin "12") (pinfunction "/CS_12") (pintype "input"))
    )
  )
)
